# monitor_3.net
KiCad netlist of a schematic drawn in EAGLE
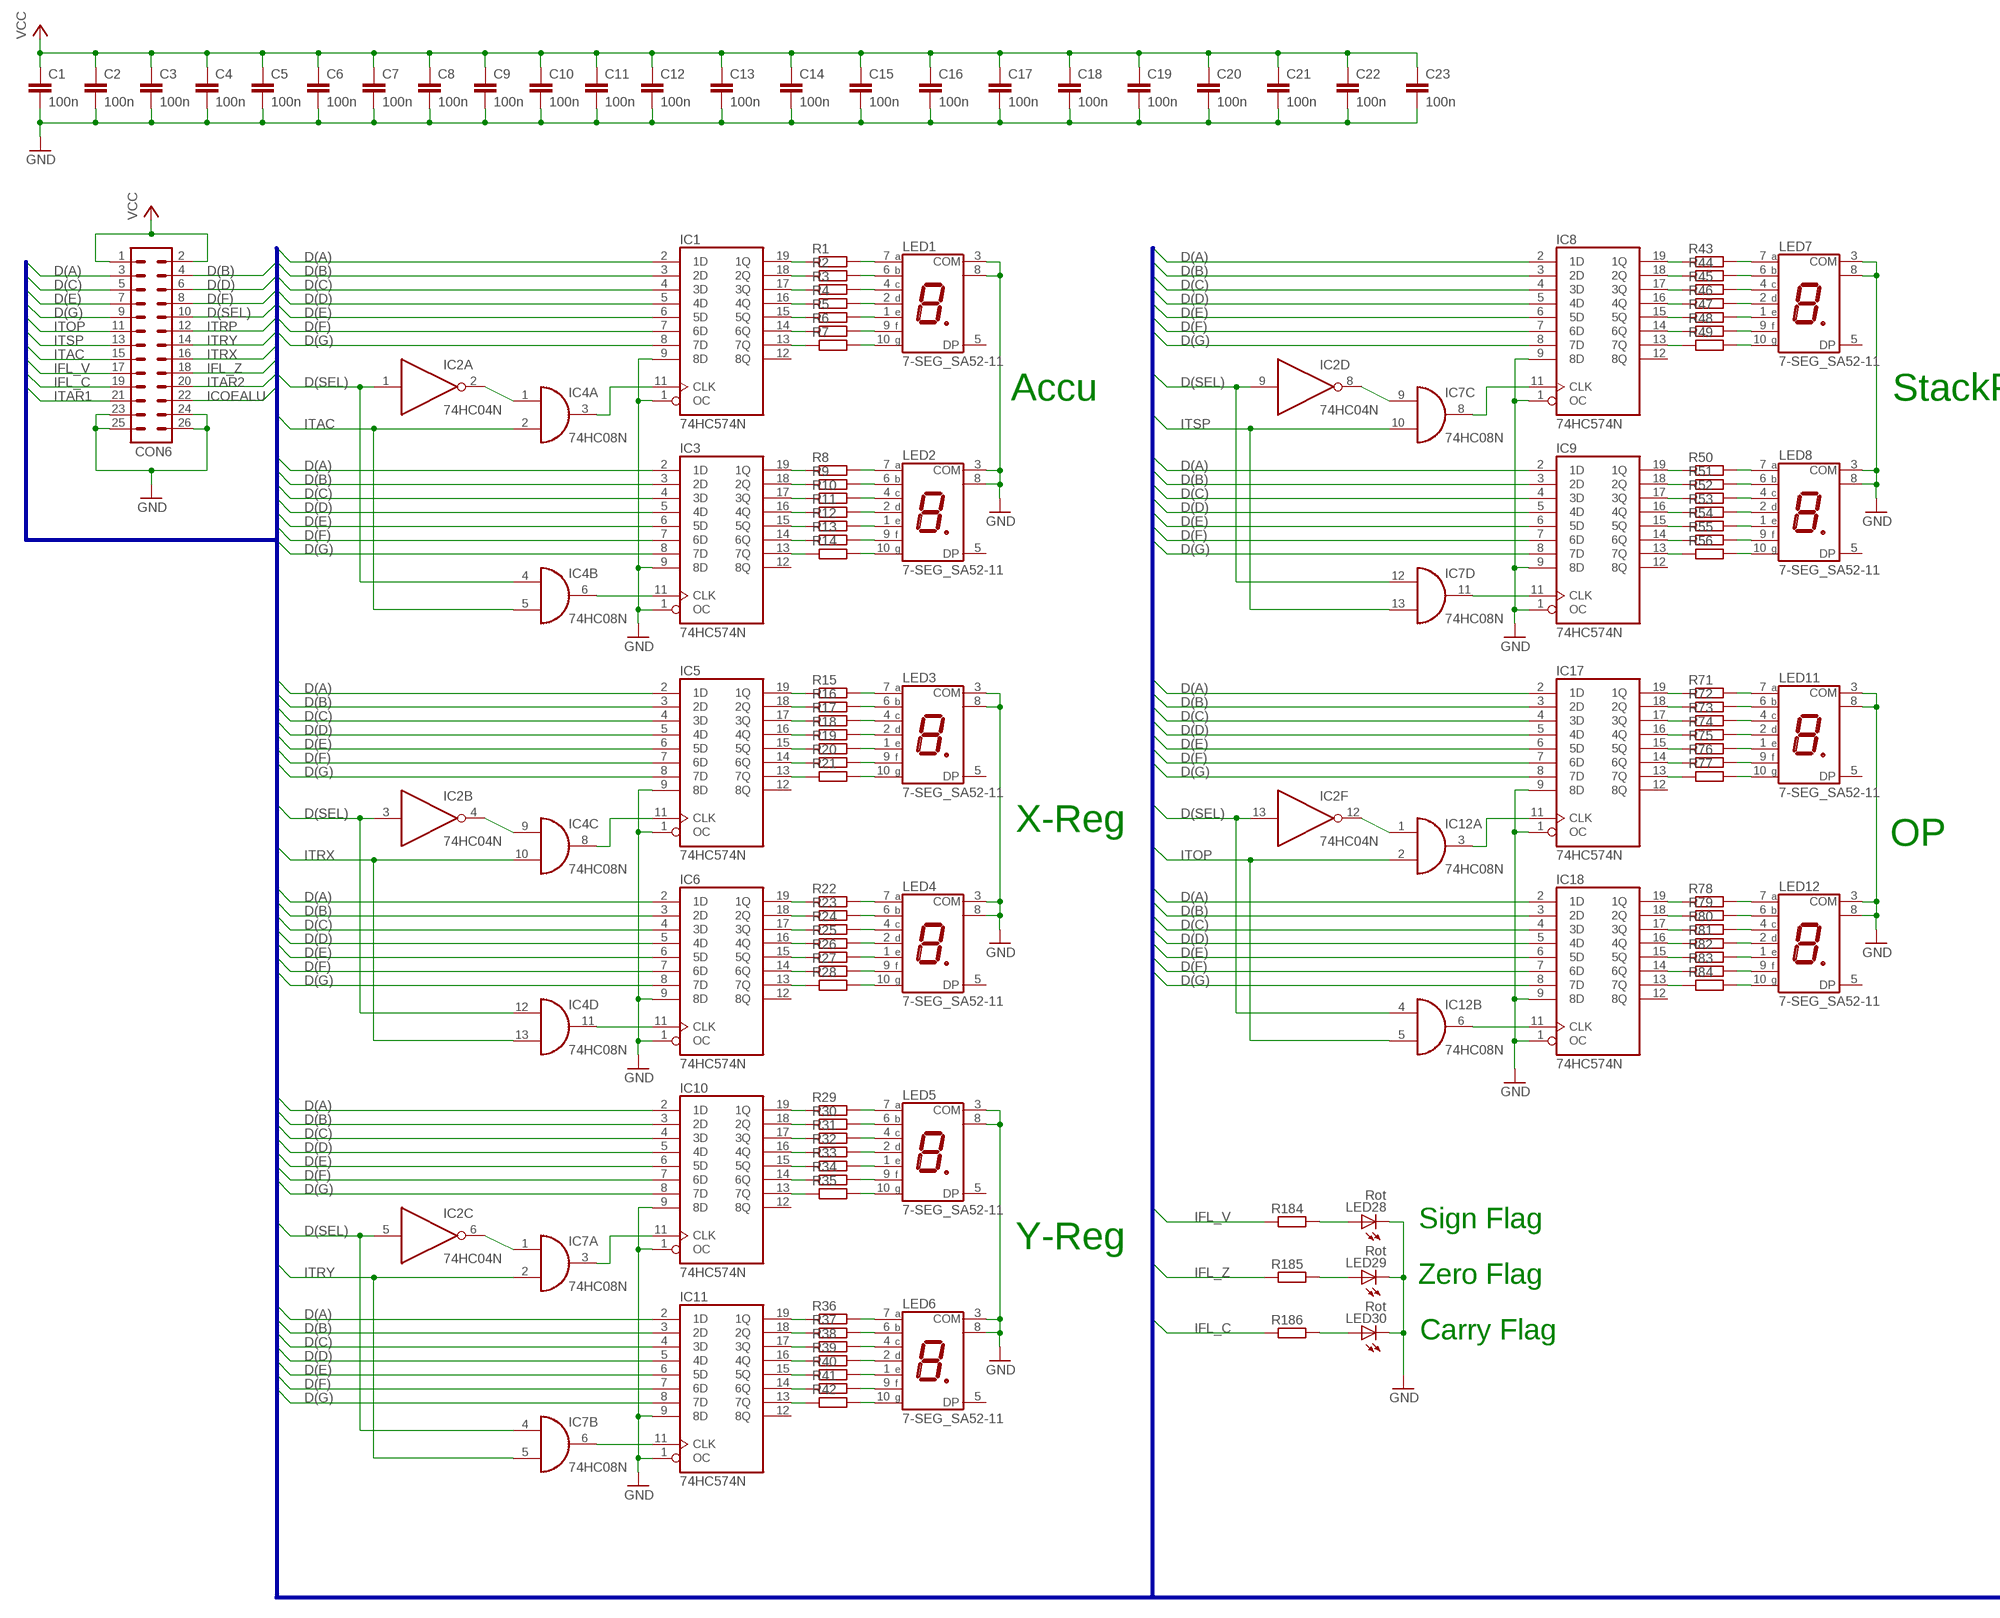
[diagram p0: schematic, sheet 1, part 1 of 2]
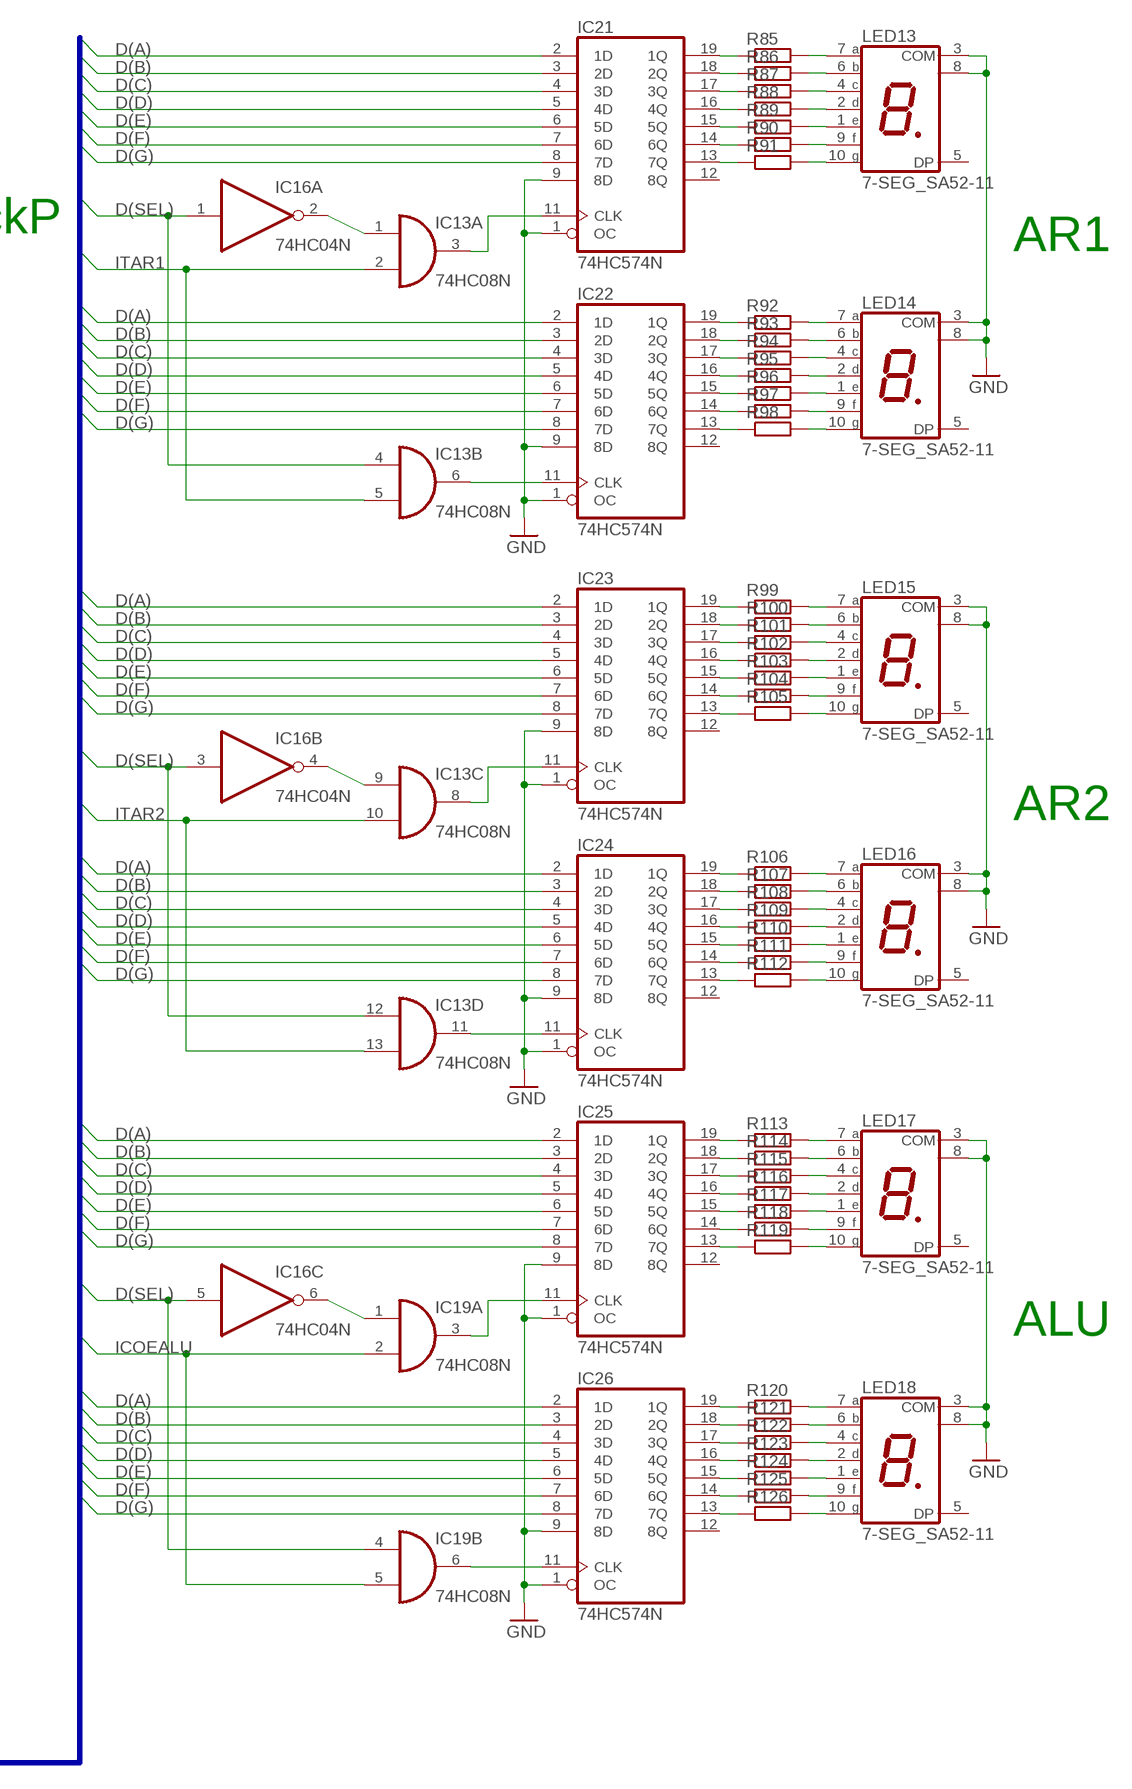
[diagram p1: schematic, sheet 1, part 2 of 2]

(export (version "E")
  (design (tool "Eeschema 10.0.6"))
  (components
    (comp (ref "C1")
      (value "100n")
      (footprint "eagle-import:C025-024X044")
      (libsource (lib "eagle-import") (part "C-EU025-024X044"))
    )
    (comp (ref "C2")
      (value "100n")
      (footprint "eagle-import:C025-024X044")
      (libsource (lib "eagle-import") (part "C-EU025-024X044"))
    )
    (comp (ref "C3")
      (value "100n")
      (footprint "eagle-import:C025-024X044")
      (libsource (lib "eagle-import") (part "C-EU025-024X044"))
    )
    (comp (ref "C4")
      (value "100n")
      (footprint "eagle-import:C025-024X044")
      (libsource (lib "eagle-import") (part "C-EU025-024X044"))
    )
    (comp (ref "C5")
      (value "100n")
      (footprint "eagle-import:C025-024X044")
      (libsource (lib "eagle-import") (part "C-EU025-024X044"))
    )
    (comp (ref "C6")
      (value "100n")
      (footprint "eagle-import:C025-024X044")
      (libsource (lib "eagle-import") (part "C-EU025-024X044"))
    )
    (comp (ref "C7")
      (value "100n")
      (footprint "eagle-import:C025-024X044")
      (libsource (lib "eagle-import") (part "C-EU025-024X044"))
    )
    (comp (ref "C8")
      (value "100n")
      (footprint "eagle-import:C025-024X044")
      (libsource (lib "eagle-import") (part "C-EU025-024X044"))
    )
    (comp (ref "C9")
      (value "100n")
      (footprint "eagle-import:C025-024X044")
      (libsource (lib "eagle-import") (part "C-EU025-024X044"))
    )
    (comp (ref "C10")
      (value "100n")
      (footprint "eagle-import:C025-024X044")
      (libsource (lib "eagle-import") (part "C-EU025-024X044"))
    )
    (comp (ref "C11")
      (value "100n")
      (footprint "eagle-import:C025-024X044")
      (libsource (lib "eagle-import") (part "C-EU025-024X044"))
    )
    (comp (ref "C12")
      (value "100n")
      (footprint "eagle-import:C025-024X044")
      (libsource (lib "eagle-import") (part "C-EU025-024X044"))
    )
    (comp (ref "C13")
      (value "100n")
      (footprint "eagle-import:C025-024X044")
      (libsource (lib "eagle-import") (part "C-EU025-024X044"))
    )
    (comp (ref "C14")
      (value "100n")
      (footprint "eagle-import:C025-024X044")
      (libsource (lib "eagle-import") (part "C-EU025-024X044"))
    )
    (comp (ref "C15")
      (value "100n")
      (footprint "eagle-import:C025-024X044")
      (libsource (lib "eagle-import") (part "C-EU025-024X044"))
    )
    (comp (ref "C16")
      (value "100n")
      (footprint "eagle-import:C025-024X044")
      (libsource (lib "eagle-import") (part "C-EU025-024X044"))
    )
    (comp (ref "C17")
      (value "100n")
      (footprint "eagle-import:C025-024X044")
      (libsource (lib "eagle-import") (part "C-EU025-024X044"))
    )
    (comp (ref "C18")
      (value "100n")
      (footprint "eagle-import:C025-024X044")
      (libsource (lib "eagle-import") (part "C-EU025-024X044"))
    )
    (comp (ref "C19")
      (value "100n")
      (footprint "eagle-import:C025-024X044")
      (libsource (lib "eagle-import") (part "C-EU025-024X044"))
    )
    (comp (ref "C20")
      (value "100n")
      (footprint "eagle-import:C025-024X044")
      (libsource (lib "eagle-import") (part "C-EU025-024X044"))
    )
    (comp (ref "C21")
      (value "100n")
      (footprint "eagle-import:C025-024X044")
      (libsource (lib "eagle-import") (part "C-EU025-024X044"))
    )
    (comp (ref "C22")
      (value "100n")
      (footprint "eagle-import:C025-024X044")
      (libsource (lib "eagle-import") (part "C-EU025-024X044"))
    )
    (comp (ref "C23")
      (value "100n")
      (footprint "eagle-import:C025-024X044")
      (libsource (lib "eagle-import") (part "C-EU025-024X044"))
    )
    (comp (ref "CON6")
      (value "ML26L")
      (footprint "eagle-import:ML26L")
      (libsource (lib "eagle-import") (part "ML26L"))
    )
    (comp (ref "IC1")
      (value "74HC574N")
      (footprint "eagle-import:DIL20")
      (libsource (lib "eagle-import") (part "74574NHC"))
    )
    (comp (ref "IC2")
      (value "74HC04N")
      (footprint "eagle-import:DIL14")
      (libsource (lib "eagle-import") (part "7404NHC"))
    )
    (comp (ref "IC3")
      (value "74HC574N")
      (footprint "eagle-import:DIL20")
      (libsource (lib "eagle-import") (part "74574NHC"))
    )
    (comp (ref "IC4")
      (value "74HC08N")
      (footprint "eagle-import:DIL14")
      (libsource (lib "eagle-import") (part "7408NHC"))
    )
    (comp (ref "IC5")
      (value "74HC574N")
      (footprint "eagle-import:DIL20")
      (libsource (lib "eagle-import") (part "74574NHC"))
    )
    (comp (ref "IC6")
      (value "74HC574N")
      (footprint "eagle-import:DIL20")
      (libsource (lib "eagle-import") (part "74574NHC"))
    )
    (comp (ref "IC7")
      (value "74HC08N")
      (footprint "eagle-import:DIL14")
      (libsource (lib "eagle-import") (part "7408NHC"))
    )
    (comp (ref "IC8")
      (value "74HC574N")
      (footprint "eagle-import:DIL20")
      (libsource (lib "eagle-import") (part "74574NHC"))
    )
    (comp (ref "IC9")
      (value "74HC574N")
      (footprint "eagle-import:DIL20")
      (libsource (lib "eagle-import") (part "74574NHC"))
    )
    (comp (ref "IC10")
      (value "74HC574N")
      (footprint "eagle-import:DIL20")
      (libsource (lib "eagle-import") (part "74574NHC"))
    )
    (comp (ref "IC11")
      (value "74HC574N")
      (footprint "eagle-import:DIL20")
      (libsource (lib "eagle-import") (part "74574NHC"))
    )
    (comp (ref "IC12")
      (value "74HC08N")
      (footprint "eagle-import:DIL14")
      (libsource (lib "eagle-import") (part "7408NHC"))
    )
    (comp (ref "IC13")
      (value "74HC08N")
      (footprint "eagle-import:DIL14")
      (libsource (lib "eagle-import") (part "7408NHC"))
    )
    (comp (ref "IC16")
      (value "74HC04N")
      (footprint "eagle-import:DIL14")
      (libsource (lib "eagle-import") (part "7404NHC"))
    )
    (comp (ref "IC17")
      (value "74HC574N")
      (footprint "eagle-import:DIL20")
      (libsource (lib "eagle-import") (part "74574NHC"))
    )
    (comp (ref "IC18")
      (value "74HC574N")
      (footprint "eagle-import:DIL20")
      (libsource (lib "eagle-import") (part "74574NHC"))
    )
    (comp (ref "IC19")
      (value "74HC08N")
      (footprint "eagle-import:DIL14")
      (libsource (lib "eagle-import") (part "7408NHC"))
    )
    (comp (ref "IC21")
      (value "74HC574N")
      (footprint "eagle-import:DIL20")
      (libsource (lib "eagle-import") (part "74574NHC"))
    )
    (comp (ref "IC22")
      (value "74HC574N")
      (footprint "eagle-import:DIL20")
      (libsource (lib "eagle-import") (part "74574NHC"))
    )
    (comp (ref "IC23")
      (value "74HC574N")
      (footprint "eagle-import:DIL20")
      (libsource (lib "eagle-import") (part "74574NHC"))
    )
    (comp (ref "IC24")
      (value "74HC574N")
      (footprint "eagle-import:DIL20")
      (libsource (lib "eagle-import") (part "74574NHC"))
    )
    (comp (ref "IC25")
      (value "74HC574N")
      (footprint "eagle-import:DIL20")
      (libsource (lib "eagle-import") (part "74574NHC"))
    )
    (comp (ref "IC26")
      (value "74HC574N")
      (footprint "eagle-import:DIL20")
      (libsource (lib "eagle-import") (part "74574NHC"))
    )
    (comp (ref "LED1")
      (value "7-SEG_SA52-11")
      (footprint "eagle-import:SA52-11")
      (libsource (lib "eagle-import") (part "7-SEG_SA52-11"))
    )
    (comp (ref "LED2")
      (value "7-SEG_SA52-11")
      (footprint "eagle-import:SA52-11")
      (libsource (lib "eagle-import") (part "7-SEG_SA52-11"))
    )
    (comp (ref "LED3")
      (value "7-SEG_SA52-11")
      (footprint "eagle-import:SA52-11")
      (libsource (lib "eagle-import") (part "7-SEG_SA52-11"))
    )
    (comp (ref "LED4")
      (value "7-SEG_SA52-11")
      (footprint "eagle-import:SA52-11")
      (libsource (lib "eagle-import") (part "7-SEG_SA52-11"))
    )
    (comp (ref "LED5")
      (value "7-SEG_SA52-11")
      (footprint "eagle-import:SA52-11")
      (libsource (lib "eagle-import") (part "7-SEG_SA52-11"))
    )
    (comp (ref "LED6")
      (value "7-SEG_SA52-11")
      (footprint "eagle-import:SA52-11")
      (libsource (lib "eagle-import") (part "7-SEG_SA52-11"))
    )
    (comp (ref "LED7")
      (value "7-SEG_SA52-11")
      (footprint "eagle-import:SA52-11")
      (libsource (lib "eagle-import") (part "7-SEG_SA52-11"))
    )
    (comp (ref "LED8")
      (value "7-SEG_SA52-11")
      (footprint "eagle-import:SA52-11")
      (libsource (lib "eagle-import") (part "7-SEG_SA52-11"))
    )
    (comp (ref "LED11")
      (value "7-SEG_SA52-11")
      (footprint "eagle-import:SA52-11")
      (libsource (lib "eagle-import") (part "7-SEG_SA52-11"))
    )
    (comp (ref "LED12")
      (value "7-SEG_SA52-11")
      (footprint "eagle-import:SA52-11")
      (libsource (lib "eagle-import") (part "7-SEG_SA52-11"))
    )
    (comp (ref "LED13")
      (value "7-SEG_SA52-11")
      (footprint "eagle-import:SA52-11")
      (libsource (lib "eagle-import") (part "7-SEG_SA52-11"))
    )
    (comp (ref "LED14")
      (value "7-SEG_SA52-11")
      (footprint "eagle-import:SA52-11")
      (libsource (lib "eagle-import") (part "7-SEG_SA52-11"))
    )
    (comp (ref "LED15")
      (value "7-SEG_SA52-11")
      (footprint "eagle-import:SA52-11")
      (libsource (lib "eagle-import") (part "7-SEG_SA52-11"))
    )
    (comp (ref "LED16")
      (value "7-SEG_SA52-11")
      (footprint "eagle-import:SA52-11")
      (libsource (lib "eagle-import") (part "7-SEG_SA52-11"))
    )
    (comp (ref "LED17")
      (value "7-SEG_SA52-11")
      (footprint "eagle-import:SA52-11")
      (libsource (lib "eagle-import") (part "7-SEG_SA52-11"))
    )
    (comp (ref "LED18")
      (value "7-SEG_SA52-11")
      (footprint "eagle-import:SA52-11")
      (libsource (lib "eagle-import") (part "7-SEG_SA52-11"))
    )
    (comp (ref "LED28")
      (value "Rot")
      (footprint "eagle-import:LED5MM")
      (libsource (lib "eagle-import") (part "LED5MM"))
    )
    (comp (ref "LED29")
      (value "Rot")
      (footprint "eagle-import:LED5MM")
      (libsource (lib "eagle-import") (part "LED5MM"))
    )
    (comp (ref "LED30")
      (value "Rot")
      (footprint "eagle-import:LED5MM")
      (libsource (lib "eagle-import") (part "LED5MM"))
    )
    (comp (ref "R1")
      (value "R-EU_0207/7")
      (footprint "eagle-import:0207_7")
      (libsource (lib "eagle-import") (part "R-EU_0207/7"))
    )
    (comp (ref "R2")
      (value "R-EU_0207/7")
      (footprint "eagle-import:0207_7")
      (libsource (lib "eagle-import") (part "R-EU_0207/7"))
    )
    (comp (ref "R3")
      (value "R-EU_0207/7")
      (footprint "eagle-import:0207_7")
      (libsource (lib "eagle-import") (part "R-EU_0207/7"))
    )
    (comp (ref "R4")
      (value "R-EU_0207/7")
      (footprint "eagle-import:0207_7")
      (libsource (lib "eagle-import") (part "R-EU_0207/7"))
    )
    (comp (ref "R5")
      (value "R-EU_0207/7")
      (footprint "eagle-import:0207_7")
      (libsource (lib "eagle-import") (part "R-EU_0207/7"))
    )
    (comp (ref "R6")
      (value "R-EU_0207/7")
      (footprint "eagle-import:0207_7")
      (libsource (lib "eagle-import") (part "R-EU_0207/7"))
    )
    (comp (ref "R7")
      (value "R-EU_0207/7")
      (footprint "eagle-import:0207_7")
      (libsource (lib "eagle-import") (part "R-EU_0207/7"))
    )
    (comp (ref "R8")
      (value "R-EU_0207/7")
      (footprint "eagle-import:0207_7")
      (libsource (lib "eagle-import") (part "R-EU_0207/7"))
    )
    (comp (ref "R9")
      (value "R-EU_0207/7")
      (footprint "eagle-import:0207_7")
      (libsource (lib "eagle-import") (part "R-EU_0207/7"))
    )
    (comp (ref "R10")
      (value "R-EU_0207/7")
      (footprint "eagle-import:0207_7")
      (libsource (lib "eagle-import") (part "R-EU_0207/7"))
    )
    (comp (ref "R11")
      (value "R-EU_0207/7")
      (footprint "eagle-import:0207_7")
      (libsource (lib "eagle-import") (part "R-EU_0207/7"))
    )
    (comp (ref "R12")
      (value "R-EU_0207/7")
      (footprint "eagle-import:0207_7")
      (libsource (lib "eagle-import") (part "R-EU_0207/7"))
    )
    (comp (ref "R13")
      (value "R-EU_0207/7")
      (footprint "eagle-import:0207_7")
      (libsource (lib "eagle-import") (part "R-EU_0207/7"))
    )
    (comp (ref "R14")
      (value "R-EU_0207/7")
      (footprint "eagle-import:0207_7")
      (libsource (lib "eagle-import") (part "R-EU_0207/7"))
    )
    (comp (ref "R15")
      (value "R-EU_0207/7")
      (footprint "eagle-import:0207_7")
      (libsource (lib "eagle-import") (part "R-EU_0207/7"))
    )
    (comp (ref "R16")
      (value "R-EU_0207/7")
      (footprint "eagle-import:0207_7")
      (libsource (lib "eagle-import") (part "R-EU_0207/7"))
    )
    (comp (ref "R17")
      (value "R-EU_0207/7")
      (footprint "eagle-import:0207_7")
      (libsource (lib "eagle-import") (part "R-EU_0207/7"))
    )
    (comp (ref "R18")
      (value "R-EU_0207/7")
      (footprint "eagle-import:0207_7")
      (libsource (lib "eagle-import") (part "R-EU_0207/7"))
    )
    (comp (ref "R19")
      (value "R-EU_0207/7")
      (footprint "eagle-import:0207_7")
      (libsource (lib "eagle-import") (part "R-EU_0207/7"))
    )
    (comp (ref "R20")
      (value "R-EU_0207/7")
      (footprint "eagle-import:0207_7")
      (libsource (lib "eagle-import") (part "R-EU_0207/7"))
    )
    (comp (ref "R21")
      (value "R-EU_0207/7")
      (footprint "eagle-import:0207_7")
      (libsource (lib "eagle-import") (part "R-EU_0207/7"))
    )
    (comp (ref "R22")
      (value "R-EU_0207/7")
      (footprint "eagle-import:0207_7")
      (libsource (lib "eagle-import") (part "R-EU_0207/7"))
    )
    (comp (ref "R23")
      (value "R-EU_0207/7")
      (footprint "eagle-import:0207_7")
      (libsource (lib "eagle-import") (part "R-EU_0207/7"))
    )
    (comp (ref "R24")
      (value "R-EU_0207/7")
      (footprint "eagle-import:0207_7")
      (libsource (lib "eagle-import") (part "R-EU_0207/7"))
    )
    (comp (ref "R25")
      (value "R-EU_0207/7")
      (footprint "eagle-import:0207_7")
      (libsource (lib "eagle-import") (part "R-EU_0207/7"))
    )
    (comp (ref "R26")
      (value "R-EU_0207/7")
      (footprint "eagle-import:0207_7")
      (libsource (lib "eagle-import") (part "R-EU_0207/7"))
    )
    (comp (ref "R27")
      (value "R-EU_0207/7")
      (footprint "eagle-import:0207_7")
      (libsource (lib "eagle-import") (part "R-EU_0207/7"))
    )
    (comp (ref "R28")
      (value "R-EU_0207/7")
      (footprint "eagle-import:0207_7")
      (libsource (lib "eagle-import") (part "R-EU_0207/7"))
    )
    (comp (ref "R29")
      (value "R-EU_0207/7")
      (footprint "eagle-import:0207_7")
      (libsource (lib "eagle-import") (part "R-EU_0207/7"))
    )
    (comp (ref "R30")
      (value "R-EU_0207/7")
      (footprint "eagle-import:0207_7")
      (libsource (lib "eagle-import") (part "R-EU_0207/7"))
    )
    (comp (ref "R31")
      (value "R-EU_0207/7")
      (footprint "eagle-import:0207_7")
      (libsource (lib "eagle-import") (part "R-EU_0207/7"))
    )
    (comp (ref "R32")
      (value "R-EU_0207/7")
      (footprint "eagle-import:0207_7")
      (libsource (lib "eagle-import") (part "R-EU_0207/7"))
    )
    (comp (ref "R33")
      (value "R-EU_0207/7")
      (footprint "eagle-import:0207_7")
      (libsource (lib "eagle-import") (part "R-EU_0207/7"))
    )
    (comp (ref "R34")
      (value "R-EU_0207/7")
      (footprint "eagle-import:0207_7")
      (libsource (lib "eagle-import") (part "R-EU_0207/7"))
    )
    (comp (ref "R35")
      (value "R-EU_0207/7")
      (footprint "eagle-import:0207_7")
      (libsource (lib "eagle-import") (part "R-EU_0207/7"))
    )
    (comp (ref "R36")
      (value "R-EU_0207/7")
      (footprint "eagle-import:0207_7")
      (libsource (lib "eagle-import") (part "R-EU_0207/7"))
    )
    (comp (ref "R37")
      (value "R-EU_0207/7")
      (footprint "eagle-import:0207_7")
      (libsource (lib "eagle-import") (part "R-EU_0207/7"))
    )
    (comp (ref "R38")
      (value "R-EU_0207/7")
      (footprint "eagle-import:0207_7")
      (libsource (lib "eagle-import") (part "R-EU_0207/7"))
    )
    (comp (ref "R39")
      (value "R-EU_0207/7")
      (footprint "eagle-import:0207_7")
      (libsource (lib "eagle-import") (part "R-EU_0207/7"))
    )
    (comp (ref "R40")
      (value "R-EU_0207/7")
      (footprint "eagle-import:0207_7")
      (libsource (lib "eagle-import") (part "R-EU_0207/7"))
    )
    (comp (ref "R41")
      (value "R-EU_0207/7")
      (footprint "eagle-import:0207_7")
      (libsource (lib "eagle-import") (part "R-EU_0207/7"))
    )
    (comp (ref "R42")
      (value "R-EU_0207/7")
      (footprint "eagle-import:0207_7")
      (libsource (lib "eagle-import") (part "R-EU_0207/7"))
    )
    (comp (ref "R43")
      (value "R-EU_0207/7")
      (footprint "eagle-import:0207_7")
      (libsource (lib "eagle-import") (part "R-EU_0207/7"))
    )
    (comp (ref "R44")
      (value "R-EU_0207/7")
      (footprint "eagle-import:0207_7")
      (libsource (lib "eagle-import") (part "R-EU_0207/7"))
    )
    (comp (ref "R45")
      (value "R-EU_0207/7")
      (footprint "eagle-import:0207_7")
      (libsource (lib "eagle-import") (part "R-EU_0207/7"))
    )
    (comp (ref "R46")
      (value "R-EU_0207/7")
      (footprint "eagle-import:0207_7")
      (libsource (lib "eagle-import") (part "R-EU_0207/7"))
    )
    (comp (ref "R47")
      (value "R-EU_0207/7")
      (footprint "eagle-import:0207_7")
      (libsource (lib "eagle-import") (part "R-EU_0207/7"))
    )
    (comp (ref "R48")
      (value "R-EU_0207/7")
      (footprint "eagle-import:0207_7")
      (libsource (lib "eagle-import") (part "R-EU_0207/7"))
    )
    (comp (ref "R49")
      (value "R-EU_0207/7")
      (footprint "eagle-import:0207_7")
      (libsource (lib "eagle-import") (part "R-EU_0207/7"))
    )
    (comp (ref "R50")
      (value "R-EU_0207/7")
      (footprint "eagle-import:0207_7")
      (libsource (lib "eagle-import") (part "R-EU_0207/7"))
    )
    (comp (ref "R51")
      (value "R-EU_0207/7")
      (footprint "eagle-import:0207_7")
      (libsource (lib "eagle-import") (part "R-EU_0207/7"))
    )
    (comp (ref "R52")
      (value "R-EU_0207/7")
      (footprint "eagle-import:0207_7")
      (libsource (lib "eagle-import") (part "R-EU_0207/7"))
    )
    (comp (ref "R53")
      (value "R-EU_0207/7")
      (footprint "eagle-import:0207_7")
      (libsource (lib "eagle-import") (part "R-EU_0207/7"))
    )
    (comp (ref "R54")
      (value "R-EU_0207/7")
      (footprint "eagle-import:0207_7")
      (libsource (lib "eagle-import") (part "R-EU_0207/7"))
    )
    (comp (ref "R55")
      (value "R-EU_0207/7")
      (footprint "eagle-import:0207_7")
      (libsource (lib "eagle-import") (part "R-EU_0207/7"))
    )
    (comp (ref "R56")
      (value "R-EU_0207/7")
      (footprint "eagle-import:0207_7")
      (libsource (lib "eagle-import") (part "R-EU_0207/7"))
    )
    (comp (ref "R71")
      (value "R-EU_0207/7")
      (footprint "eagle-import:0207_7")
      (libsource (lib "eagle-import") (part "R-EU_0207/7"))
    )
    (comp (ref "R72")
      (value "R-EU_0207/7")
      (footprint "eagle-import:0207_7")
      (libsource (lib "eagle-import") (part "R-EU_0207/7"))
    )
    (comp (ref "R73")
      (value "R-EU_0207/7")
      (footprint "eagle-import:0207_7")
      (libsource (lib "eagle-import") (part "R-EU_0207/7"))
    )
    (comp (ref "R74")
      (value "R-EU_0207/7")
      (footprint "eagle-import:0207_7")
      (libsource (lib "eagle-import") (part "R-EU_0207/7"))
    )
    (comp (ref "R75")
      (value "R-EU_0207/7")
      (footprint "eagle-import:0207_7")
      (libsource (lib "eagle-import") (part "R-EU_0207/7"))
    )
    (comp (ref "R76")
      (value "R-EU_0207/7")
      (footprint "eagle-import:0207_7")
      (libsource (lib "eagle-import") (part "R-EU_0207/7"))
    )
    (comp (ref "R77")
      (value "R-EU_0207/7")
      (footprint "eagle-import:0207_7")
      (libsource (lib "eagle-import") (part "R-EU_0207/7"))
    )
    (comp (ref "R78")
      (value "R-EU_0207/7")
      (footprint "eagle-import:0207_7")
      (libsource (lib "eagle-import") (part "R-EU_0207/7"))
    )
    (comp (ref "R79")
      (value "R-EU_0207/7")
      (footprint "eagle-import:0207_7")
      (libsource (lib "eagle-import") (part "R-EU_0207/7"))
    )
    (comp (ref "R80")
      (value "R-EU_0207/7")
      (footprint "eagle-import:0207_7")
      (libsource (lib "eagle-import") (part "R-EU_0207/7"))
    )
    (comp (ref "R81")
      (value "R-EU_0207/7")
      (footprint "eagle-import:0207_7")
      (libsource (lib "eagle-import") (part "R-EU_0207/7"))
    )
    (comp (ref "R82")
      (value "R-EU_0207/7")
      (footprint "eagle-import:0207_7")
      (libsource (lib "eagle-import") (part "R-EU_0207/7"))
    )
    (comp (ref "R83")
      (value "R-EU_0207/7")
      (footprint "eagle-import:0207_7")
      (libsource (lib "eagle-import") (part "R-EU_0207/7"))
    )
    (comp (ref "R84")
      (value "R-EU_0207/7")
      (footprint "eagle-import:0207_7")
      (libsource (lib "eagle-import") (part "R-EU_0207/7"))
    )
    (comp (ref "R85")
      (value "R-EU_0207/7")
      (footprint "eagle-import:0207_7")
      (libsource (lib "eagle-import") (part "R-EU_0207/7"))
    )
    (comp (ref "R86")
      (value "R-EU_0207/7")
      (footprint "eagle-import:0207_7")
      (libsource (lib "eagle-import") (part "R-EU_0207/7"))
    )
    (comp (ref "R87")
      (value "R-EU_0207/7")
      (footprint "eagle-import:0207_7")
      (libsource (lib "eagle-import") (part "R-EU_0207/7"))
    )
    (comp (ref "R88")
      (value "R-EU_0207/7")
      (footprint "eagle-import:0207_7")
      (libsource (lib "eagle-import") (part "R-EU_0207/7"))
    )
    (comp (ref "R89")
      (value "R-EU_0207/7")
      (footprint "eagle-import:0207_7")
      (libsource (lib "eagle-import") (part "R-EU_0207/7"))
    )
    (comp (ref "R90")
      (value "R-EU_0207/7")
      (footprint "eagle-import:0207_7")
      (libsource (lib "eagle-import") (part "R-EU_0207/7"))
    )
    (comp (ref "R91")
      (value "R-EU_0207/7")
      (footprint "eagle-import:0207_7")
      (libsource (lib "eagle-import") (part "R-EU_0207/7"))
    )
    (comp (ref "R92")
      (value "R-EU_0207/7")
      (footprint "eagle-import:0207_7")
      (libsource (lib "eagle-import") (part "R-EU_0207/7"))
    )
    (comp (ref "R93")
      (value "R-EU_0207/7")
      (footprint "eagle-import:0207_7")
      (libsource (lib "eagle-import") (part "R-EU_0207/7"))
    )
    (comp (ref "R94")
      (value "R-EU_0207/7")
      (footprint "eagle-import:0207_7")
      (libsource (lib "eagle-import") (part "R-EU_0207/7"))
    )
    (comp (ref "R95")
      (value "R-EU_0207/7")
      (footprint "eagle-import:0207_7")
      (libsource (lib "eagle-import") (part "R-EU_0207/7"))
    )
    (comp (ref "R96")
      (value "R-EU_0207/7")
      (footprint "eagle-import:0207_7")
      (libsource (lib "eagle-import") (part "R-EU_0207/7"))
    )
    (comp (ref "R97")
      (value "R-EU_0207/7")
      (footprint "eagle-import:0207_7")
      (libsource (lib "eagle-import") (part "R-EU_0207/7"))
    )
    (comp (ref "R98")
      (value "R-EU_0207/7")
      (footprint "eagle-import:0207_7")
      (libsource (lib "eagle-import") (part "R-EU_0207/7"))
    )
    (comp (ref "R99")
      (value "R-EU_0207/7")
      (footprint "eagle-import:0207_7")
      (libsource (lib "eagle-import") (part "R-EU_0207/7"))
    )
    (comp (ref "R100")
      (value "R-EU_0207/7")
      (footprint "eagle-import:0207_7")
      (libsource (lib "eagle-import") (part "R-EU_0207/7"))
    )
    (comp (ref "R101")
      (value "R-EU_0207/7")
      (footprint "eagle-import:0207_7")
      (libsource (lib "eagle-import") (part "R-EU_0207/7"))
    )
    (comp (ref "R102")
      (value "R-EU_0207/7")
      (footprint "eagle-import:0207_7")
      (libsource (lib "eagle-import") (part "R-EU_0207/7"))
    )
    (comp (ref "R103")
      (value "R-EU_0207/7")
      (footprint "eagle-import:0207_7")
      (libsource (lib "eagle-import") (part "R-EU_0207/7"))
    )
    (comp (ref "R104")
      (value "R-EU_0207/7")
      (footprint "eagle-import:0207_7")
      (libsource (lib "eagle-import") (part "R-EU_0207/7"))
    )
    (comp (ref "R105")
      (value "R-EU_0207/7")
      (footprint "eagle-import:0207_7")
      (libsource (lib "eagle-import") (part "R-EU_0207/7"))
    )
    (comp (ref "R106")
      (value "R-EU_0207/7")
      (footprint "eagle-import:0207_7")
      (libsource (lib "eagle-import") (part "R-EU_0207/7"))
    )
    (comp (ref "R107")
      (value "R-EU_0207/7")
      (footprint "eagle-import:0207_7")
      (libsource (lib "eagle-import") (part "R-EU_0207/7"))
    )
    (comp (ref "R108")
      (value "R-EU_0207/7")
      (footprint "eagle-import:0207_7")
      (libsource (lib "eagle-import") (part "R-EU_0207/7"))
    )
    (comp (ref "R109")
      (value "R-EU_0207/7")
      (footprint "eagle-import:0207_7")
      (libsource (lib "eagle-import") (part "R-EU_0207/7"))
    )
    (comp (ref "R110")
      (value "R-EU_0207/7")
      (footprint "eagle-import:0207_7")
      (libsource (lib "eagle-import") (part "R-EU_0207/7"))
    )
    (comp (ref "R111")
      (value "R-EU_0207/7")
      (footprint "eagle-import:0207_7")
      (libsource (lib "eagle-import") (part "R-EU_0207/7"))
    )
    (comp (ref "R112")
      (value "R-EU_0207/7")
      (footprint "eagle-import:0207_7")
      (libsource (lib "eagle-import") (part "R-EU_0207/7"))
    )
    (comp (ref "R113")
      (value "R-EU_0207/7")
      (footprint "eagle-import:0207_7")
      (libsource (lib "eagle-import") (part "R-EU_0207/7"))
    )
    (comp (ref "R114")
      (value "R-EU_0207/7")
      (footprint "eagle-import:0207_7")
      (libsource (lib "eagle-import") (part "R-EU_0207/7"))
    )
    (comp (ref "R115")
      (value "R-EU_0207/7")
      (footprint "eagle-import:0207_7")
      (libsource (lib "eagle-import") (part "R-EU_0207/7"))
    )
    (comp (ref "R116")
      (value "R-EU_0207/7")
      (footprint "eagle-import:0207_7")
      (libsource (lib "eagle-import") (part "R-EU_0207/7"))
    )
    (comp (ref "R117")
      (value "R-EU_0207/7")
      (footprint "eagle-import:0207_7")
      (libsource (lib "eagle-import") (part "R-EU_0207/7"))
    )
    (comp (ref "R118")
      (value "R-EU_0207/7")
      (footprint "eagle-import:0207_7")
      (libsource (lib "eagle-import") (part "R-EU_0207/7"))
    )
    (comp (ref "R119")
      (value "R-EU_0207/7")
      (footprint "eagle-import:0207_7")
      (libsource (lib "eagle-import") (part "R-EU_0207/7"))
    )
    (comp (ref "R120")
      (value "R-EU_0207/7")
      (footprint "eagle-import:0207_7")
      (libsource (lib "eagle-import") (part "R-EU_0207/7"))
    )
    (comp (ref "R121")
      (value "R-EU_0207/7")
      (footprint "eagle-import:0207_7")
      (libsource (lib "eagle-import") (part "R-EU_0207/7"))
    )
    (comp (ref "R122")
      (value "R-EU_0207/7")
      (footprint "eagle-import:0207_7")
      (libsource (lib "eagle-import") (part "R-EU_0207/7"))
    )
    (comp (ref "R123")
      (value "R-EU_0207/7")
      (footprint "eagle-import:0207_7")
      (libsource (lib "eagle-import") (part "R-EU_0207/7"))
    )
    (comp (ref "R124")
      (value "R-EU_0207/7")
      (footprint "eagle-import:0207_7")
      (libsource (lib "eagle-import") (part "R-EU_0207/7"))
    )
    (comp (ref "R125")
      (value "R-EU_0207/7")
      (footprint "eagle-import:0207_7")
      (libsource (lib "eagle-import") (part "R-EU_0207/7"))
    )
    (comp (ref "R126")
      (value "R-EU_0207/7")
      (footprint "eagle-import:0207_7")
      (libsource (lib "eagle-import") (part "R-EU_0207/7"))
    )
    (comp (ref "R184")
      (value "R-EU_0207/7")
      (footprint "eagle-import:0207_7")
      (libsource (lib "eagle-import") (part "R-EU_0207/7"))
    )
    (comp (ref "R185")
      (value "R-EU_0207/7")
      (footprint "eagle-import:0207_7")
      (libsource (lib "eagle-import") (part "R-EU_0207/7"))
    )
    (comp (ref "R186")
      (value "R-EU_0207/7")
      (footprint "eagle-import:0207_7")
      (libsource (lib "eagle-import") (part "R-EU_0207/7"))
    )
  )
  (nets
    (net (code "1") (name "/D(A)") (class "Default")
      (node (ref "CON6") (pin "3") (pinfunction "3_3") (pintype "passive"))
      (node (ref "IC1") (pin "2") (pinfunction "1D_2") (pintype "input"))
      (node (ref "IC10") (pin "2") (pinfunction "1D_2") (pintype "input"))
      (node (ref "IC11") (pin "2") (pinfunction "1D_2") (pintype "input"))
      (node (ref "IC17") (pin "2") (pinfunction "1D_2") (pintype "input"))
      (node (ref "IC18") (pin "2") (pinfunction "1D_2") (pintype "input"))
      (node (ref "IC21") (pin "2") (pinfunction "1D_2") (pintype "input"))
      (node (ref "IC22") (pin "2") (pinfunction "1D_2") (pintype "input"))
      (node (ref "IC23") (pin "2") (pinfunction "1D_2") (pintype "input"))
      (node (ref "IC24") (pin "2") (pinfunction "1D_2") (pintype "input"))
      (node (ref "IC25") (pin "2") (pinfunction "1D_2") (pintype "input"))
      (node (ref "IC26") (pin "2") (pinfunction "1D_2") (pintype "input"))
      (node (ref "IC3") (pin "2") (pinfunction "1D_2") (pintype "input"))
      (node (ref "IC5") (pin "2") (pinfunction "1D_2") (pintype "input"))
      (node (ref "IC6") (pin "2") (pinfunction "1D_2") (pintype "input"))
      (node (ref "IC8") (pin "2") (pinfunction "1D_2") (pintype "input"))
      (node (ref "IC9") (pin "2") (pinfunction "1D_2") (pintype "input"))
    )
    (net (code "2") (name "/D(B)") (class "Default")
      (node (ref "CON6") (pin "4") (pinfunction "4_4") (pintype "passive"))
      (node (ref "IC1") (pin "3") (pinfunction "2D_3") (pintype "input"))
      (node (ref "IC10") (pin "3") (pinfunction "2D_3") (pintype "input"))
      (node (ref "IC11") (pin "3") (pinfunction "2D_3") (pintype "input"))
      (node (ref "IC17") (pin "3") (pinfunction "2D_3") (pintype "input"))
      (node (ref "IC18") (pin "3") (pinfunction "2D_3") (pintype "input"))
      (node (ref "IC21") (pin "3") (pinfunction "2D_3") (pintype "input"))
      (node (ref "IC22") (pin "3") (pinfunction "2D_3") (pintype "input"))
      (node (ref "IC23") (pin "3") (pinfunction "2D_3") (pintype "input"))
      (node (ref "IC24") (pin "3") (pinfunction "2D_3") (pintype "input"))
      (node (ref "IC25") (pin "3") (pinfunction "2D_3") (pintype "input"))
      (node (ref "IC26") (pin "3") (pinfunction "2D_3") (pintype "input"))
      (node (ref "IC3") (pin "3") (pinfunction "2D_3") (pintype "input"))
      (node (ref "IC5") (pin "3") (pinfunction "2D_3") (pintype "input"))
      (node (ref "IC6") (pin "3") (pinfunction "2D_3") (pintype "input"))
      (node (ref "IC8") (pin "3") (pinfunction "2D_3") (pintype "input"))
      (node (ref "IC9") (pin "3") (pinfunction "2D_3") (pintype "input"))
    )
    (net (code "3") (name "/D(C)") (class "Default")
      (node (ref "CON6") (pin "5") (pinfunction "5_5") (pintype "passive"))
      (node (ref "IC1") (pin "4") (pinfunction "3D_4") (pintype "input"))
      (node (ref "IC10") (pin "4") (pinfunction "3D_4") (pintype "input"))
      (node (ref "IC11") (pin "4") (pinfunction "3D_4") (pintype "input"))
      (node (ref "IC17") (pin "4") (pinfunction "3D_4") (pintype "input"))
      (node (ref "IC18") (pin "4") (pinfunction "3D_4") (pintype "input"))
      (node (ref "IC21") (pin "4") (pinfunction "3D_4") (pintype "input"))
      (node (ref "IC22") (pin "4") (pinfunction "3D_4") (pintype "input"))
      (node (ref "IC23") (pin "4") (pinfunction "3D_4") (pintype "input"))
      (node (ref "IC24") (pin "4") (pinfunction "3D_4") (pintype "input"))
      (node (ref "IC25") (pin "4") (pinfunction "3D_4") (pintype "input"))
      (node (ref "IC26") (pin "4") (pinfunction "3D_4") (pintype "input"))
      (node (ref "IC3") (pin "4") (pinfunction "3D_4") (pintype "input"))
      (node (ref "IC5") (pin "4") (pinfunction "3D_4") (pintype "input"))
      (node (ref "IC6") (pin "4") (pinfunction "3D_4") (pintype "input"))
      (node (ref "IC8") (pin "4") (pinfunction "3D_4") (pintype "input"))
      (node (ref "IC9") (pin "4") (pinfunction "3D_4") (pintype "input"))
    )
    (net (code "4") (name "/D(D)") (class "Default")
      (node (ref "CON6") (pin "6") (pinfunction "6_6") (pintype "passive"))
      (node (ref "IC1") (pin "5") (pinfunction "4D_5") (pintype "input"))
      (node (ref "IC10") (pin "5") (pinfunction "4D_5") (pintype "input"))
      (node (ref "IC11") (pin "5") (pinfunction "4D_5") (pintype "input"))
      (node (ref "IC17") (pin "5") (pinfunction "4D_5") (pintype "input"))
      (node (ref "IC18") (pin "5") (pinfunction "4D_5") (pintype "input"))
      (node (ref "IC21") (pin "5") (pinfunction "4D_5") (pintype "input"))
      (node (ref "IC22") (pin "5") (pinfunction "4D_5") (pintype "input"))
      (node (ref "IC23") (pin "5") (pinfunction "4D_5") (pintype "input"))
      (node (ref "IC24") (pin "5") (pinfunction "4D_5") (pintype "input"))
      (node (ref "IC25") (pin "5") (pinfunction "4D_5") (pintype "input"))
      (node (ref "IC26") (pin "5") (pinfunction "4D_5") (pintype "input"))
      (node (ref "IC3") (pin "5") (pinfunction "4D_5") (pintype "input"))
      (node (ref "IC5") (pin "5") (pinfunction "4D_5") (pintype "input"))
      (node (ref "IC6") (pin "5") (pinfunction "4D_5") (pintype "input"))
      (node (ref "IC8") (pin "5") (pinfunction "4D_5") (pintype "input"))
      (node (ref "IC9") (pin "5") (pinfunction "4D_5") (pintype "input"))
    )
    (net (code "5") (name "/D(E)") (class "Default")
      (node (ref "CON6") (pin "7") (pinfunction "7_7") (pintype "passive"))
      (node (ref "IC1") (pin "6") (pinfunction "5D_6") (pintype "input"))
      (node (ref "IC10") (pin "6") (pinfunction "5D_6") (pintype "input"))
      (node (ref "IC11") (pin "6") (pinfunction "5D_6") (pintype "input"))
      (node (ref "IC17") (pin "6") (pinfunction "5D_6") (pintype "input"))
      (node (ref "IC18") (pin "6") (pinfunction "5D_6") (pintype "input"))
      (node (ref "IC21") (pin "6") (pinfunction "5D_6") (pintype "input"))
      (node (ref "IC22") (pin "6") (pinfunction "5D_6") (pintype "input"))
      (node (ref "IC23") (pin "6") (pinfunction "5D_6") (pintype "input"))
      (node (ref "IC24") (pin "6") (pinfunction "5D_6") (pintype "input"))
      (node (ref "IC25") (pin "6") (pinfunction "5D_6") (pintype "input"))
      (node (ref "IC26") (pin "6") (pinfunction "5D_6") (pintype "input"))
      (node (ref "IC3") (pin "6") (pinfunction "5D_6") (pintype "input"))
      (node (ref "IC5") (pin "6") (pinfunction "5D_6") (pintype "input"))
      (node (ref "IC6") (pin "6") (pinfunction "5D_6") (pintype "input"))
      (node (ref "IC8") (pin "6") (pinfunction "5D_6") (pintype "input"))
      (node (ref "IC9") (pin "6") (pinfunction "5D_6") (pintype "input"))
    )
    (net (code "6") (name "/D(F)") (class "Default")
      (node (ref "CON6") (pin "8") (pinfunction "8_8") (pintype "passive"))
      (node (ref "IC1") (pin "7") (pinfunction "6D_7") (pintype "input"))
      (node (ref "IC10") (pin "7") (pinfunction "6D_7") (pintype "input"))
      (node (ref "IC11") (pin "7") (pinfunction "6D_7") (pintype "input"))
      (node (ref "IC17") (pin "7") (pinfunction "6D_7") (pintype "input"))
      (node (ref "IC18") (pin "7") (pinfunction "6D_7") (pintype "input"))
      (node (ref "IC21") (pin "7") (pinfunction "6D_7") (pintype "input"))
      (node (ref "IC22") (pin "7") (pinfunction "6D_7") (pintype "input"))
      (node (ref "IC23") (pin "7") (pinfunction "6D_7") (pintype "input"))
      (node (ref "IC24") (pin "7") (pinfunction "6D_7") (pintype "input"))
      (node (ref "IC25") (pin "7") (pinfunction "6D_7") (pintype "input"))
      (node (ref "IC26") (pin "7") (pinfunction "6D_7") (pintype "input"))
      (node (ref "IC3") (pin "7") (pinfunction "6D_7") (pintype "input"))
      (node (ref "IC5") (pin "7") (pinfunction "6D_7") (pintype "input"))
      (node (ref "IC6") (pin "7") (pinfunction "6D_7") (pintype "input"))
      (node (ref "IC8") (pin "7") (pinfunction "6D_7") (pintype "input"))
      (node (ref "IC9") (pin "7") (pinfunction "6D_7") (pintype "input"))
    )
    (net (code "7") (name "/D(G)") (class "Default")
      (node (ref "CON6") (pin "9") (pinfunction "9_9") (pintype "passive"))
      (node (ref "IC1") (pin "8") (pinfunction "7D_8") (pintype "input"))
      (node (ref "IC10") (pin "8") (pinfunction "7D_8") (pintype "input"))
      (node (ref "IC11") (pin "8") (pinfunction "7D_8") (pintype "input"))
      (node (ref "IC17") (pin "8") (pinfunction "7D_8") (pintype "input"))
      (node (ref "IC18") (pin "8") (pinfunction "7D_8") (pintype "input"))
      (node (ref "IC21") (pin "8") (pinfunction "7D_8") (pintype "input"))
      (node (ref "IC22") (pin "8") (pinfunction "7D_8") (pintype "input"))
      (node (ref "IC23") (pin "8") (pinfunction "7D_8") (pintype "input"))
      (node (ref "IC24") (pin "8") (pinfunction "7D_8") (pintype "input"))
      (node (ref "IC25") (pin "8") (pinfunction "7D_8") (pintype "input"))
      (node (ref "IC26") (pin "8") (pinfunction "7D_8") (pintype "input"))
      (node (ref "IC3") (pin "8") (pinfunction "7D_8") (pintype "input"))
      (node (ref "IC5") (pin "8") (pinfunction "7D_8") (pintype "input"))
      (node (ref "IC6") (pin "8") (pinfunction "7D_8") (pintype "input"))
      (node (ref "IC8") (pin "8") (pinfunction "7D_8") (pintype "input"))
      (node (ref "IC9") (pin "8") (pinfunction "7D_8") (pintype "input"))
    )
    (net (code "8") (name "/D(SEL)") (class "Default")
      (node (ref "CON6") (pin "10") (pinfunction "10_10") (pintype "passive"))
      (node (ref "IC12") (pin "4") (pinfunction "I0_4") (pintype "input"))
      (node (ref "IC13") (pin "12") (pinfunction "I0_12") (pintype "input"))
      (node (ref "IC13") (pin "4") (pinfunction "I0_4") (pintype "input"))
      (node (ref "IC16") (pin "1") (pinfunction "I_1") (pintype "input"))
      (node (ref "IC16") (pin "3") (pinfunction "I_3") (pintype "input"))
      (node (ref "IC16") (pin "5") (pinfunction "I_5") (pintype "input"))
      (node (ref "IC19") (pin "4") (pinfunction "I0_4") (pintype "input"))
      (node (ref "IC2") (pin "1") (pinfunction "I_1") (pintype "input"))
      (node (ref "IC2") (pin "13") (pinfunction "I_13") (pintype "input"))
      (node (ref "IC2") (pin "3") (pinfunction "I_3") (pintype "input"))
      (node (ref "IC2") (pin "5") (pinfunction "I_5") (pintype "input"))
      (node (ref "IC2") (pin "9") (pinfunction "I_9") (pintype "input"))
      (node (ref "IC4") (pin "12") (pinfunction "I0_12") (pintype "input"))
      (node (ref "IC4") (pin "4") (pinfunction "I0_4") (pintype "input"))
      (node (ref "IC7") (pin "12") (pinfunction "I0_12") (pintype "input"))
      (node (ref "IC7") (pin "4") (pinfunction "I0_4") (pintype "input"))
    )
    (net (code "9") (name "/ICOEALU") (class "Default")
      (node (ref "CON6") (pin "22") (pinfunction "22_22") (pintype "passive"))
      (node (ref "IC19") (pin "2") (pinfunction "I1_2") (pintype "input"))
      (node (ref "IC19") (pin "5") (pinfunction "I1_5") (pintype "input"))
    )
    (net (code "10") (name "/IFL_C") (class "Default")
      (node (ref "CON6") (pin "19") (pinfunction "19_19") (pintype "passive"))
      (node (ref "R186") (pin "1") (pinfunction "1_1") (pintype "passive"))
    )
    (net (code "11") (name "/IFL_V") (class "Default")
      (node (ref "CON6") (pin "17") (pinfunction "17_17") (pintype "passive"))
      (node (ref "R184") (pin "1") (pinfunction "1_1") (pintype "passive"))
    )
    (net (code "12") (name "/IFL_Z") (class "Default")
      (node (ref "CON6") (pin "18") (pinfunction "18_18") (pintype "passive"))
      (node (ref "R185") (pin "1") (pinfunction "1_1") (pintype "passive"))
    )
    (net (code "13") (name "/ITAC") (class "Default")
      (node (ref "CON6") (pin "15") (pinfunction "15_15") (pintype "passive"))
      (node (ref "IC4") (pin "2") (pinfunction "I1_2") (pintype "input"))
      (node (ref "IC4") (pin "5") (pinfunction "I1_5") (pintype "input"))
    )
    (net (code "14") (name "/ITAR1") (class "Default")
      (node (ref "CON6") (pin "21") (pinfunction "21_21") (pintype "passive"))
      (node (ref "IC13") (pin "2") (pinfunction "I1_2") (pintype "input"))
      (node (ref "IC13") (pin "5") (pinfunction "I1_5") (pintype "input"))
    )
    (net (code "15") (name "/ITAR2") (class "Default")
      (node (ref "CON6") (pin "20") (pinfunction "20_20") (pintype "passive"))
      (node (ref "IC13") (pin "10") (pinfunction "I1_10") (pintype "input"))
      (node (ref "IC13") (pin "13") (pinfunction "I1_13") (pintype "input"))
    )
    (net (code "16") (name "/ITOP") (class "Default")
      (node (ref "CON6") (pin "11") (pinfunction "11_11") (pintype "passive"))
      (node (ref "IC12") (pin "2") (pinfunction "I1_2") (pintype "input"))
      (node (ref "IC12") (pin "5") (pinfunction "I1_5") (pintype "input"))
    )
    (net (code "17") (name "/ITRP") (class "Default")
      (node (ref "CON6") (pin "12") (pinfunction "12_12") (pintype "passive"))
    )
    (net (code "18") (name "/ITRX") (class "Default")
      (node (ref "CON6") (pin "16") (pinfunction "16_16") (pintype "passive"))
      (node (ref "IC4") (pin "10") (pinfunction "I1_10") (pintype "input"))
      (node (ref "IC4") (pin "13") (pinfunction "I1_13") (pintype "input"))
    )
    (net (code "19") (name "/ITRY") (class "Default")
      (node (ref "CON6") (pin "14") (pinfunction "14_14") (pintype "passive"))
      (node (ref "IC7") (pin "2") (pinfunction "I1_2") (pintype "input"))
      (node (ref "IC7") (pin "5") (pinfunction "I1_5") (pintype "input"))
    )
    (net (code "20") (name "/ITSP") (class "Default")
      (node (ref "CON6") (pin "13") (pinfunction "13_13") (pintype "passive"))
      (node (ref "IC7") (pin "10") (pinfunction "I1_10") (pintype "input"))
      (node (ref "IC7") (pin "13") (pinfunction "I1_13") (pintype "input"))
    )
    (net (code "21") (name "GND") (class "Default")
      (node (ref "C1") (pin "2") (pinfunction "2_2") (pintype "passive"))
      (node (ref "C10") (pin "2") (pinfunction "2_2") (pintype "passive"))
      (node (ref "C11") (pin "2") (pinfunction "2_2") (pintype "passive"))
      (node (ref "C12") (pin "2") (pinfunction "2_2") (pintype "passive"))
      (node (ref "C13") (pin "2") (pinfunction "2_2") (pintype "passive"))
      (node (ref "C14") (pin "2") (pinfunction "2_2") (pintype "passive"))
      (node (ref "C15") (pin "2") (pinfunction "2_2") (pintype "passive"))
      (node (ref "C16") (pin "2") (pinfunction "2_2") (pintype "passive"))
      (node (ref "C17") (pin "2") (pinfunction "2_2") (pintype "passive"))
      (node (ref "C18") (pin "2") (pinfunction "2_2") (pintype "passive"))
      (node (ref "C19") (pin "2") (pinfunction "2_2") (pintype "passive"))
      (node (ref "C2") (pin "2") (pinfunction "2_2") (pintype "passive"))
      (node (ref "C20") (pin "2") (pinfunction "2_2") (pintype "passive"))
      (node (ref "C21") (pin "2") (pinfunction "2_2") (pintype "passive"))
      (node (ref "C22") (pin "2") (pinfunction "2_2") (pintype "passive"))
      (node (ref "C23") (pin "2") (pinfunction "2_2") (pintype "passive"))
      (node (ref "C3") (pin "2") (pinfunction "2_2") (pintype "passive"))
      (node (ref "C4") (pin "2") (pinfunction "2_2") (pintype "passive"))
      (node (ref "C5") (pin "2") (pinfunction "2_2") (pintype "passive"))
      (node (ref "C6") (pin "2") (pinfunction "2_2") (pintype "passive"))
      (node (ref "C7") (pin "2") (pinfunction "2_2") (pintype "passive"))
      (node (ref "C8") (pin "2") (pinfunction "2_2") (pintype "passive"))
      (node (ref "C9") (pin "2") (pinfunction "2_2") (pintype "passive"))
      (node (ref "CON6") (pin "23") (pinfunction "23_23") (pintype "passive"))
      (node (ref "CON6") (pin "24") (pinfunction "24_24") (pintype "passive"))
      (node (ref "CON6") (pin "25") (pinfunction "25_25") (pintype "passive"))
      (node (ref "CON6") (pin "26") (pinfunction "26_26") (pintype "passive"))
      (node (ref "IC1") (pin "1") (pinfunction "OC_1") (pintype "input"))
      (node (ref "IC1") (pin "9") (pinfunction "8D_9") (pintype "input"))
      (node (ref "IC10") (pin "1") (pinfunction "OC_1") (pintype "input"))
      (node (ref "IC10") (pin "9") (pinfunction "8D_9") (pintype "input"))
      (node (ref "IC11") (pin "1") (pinfunction "OC_1") (pintype "input"))
      (node (ref "IC11") (pin "9") (pinfunction "8D_9") (pintype "input"))
      (node (ref "IC17") (pin "1") (pinfunction "OC_1") (pintype "input"))
      (node (ref "IC17") (pin "9") (pinfunction "8D_9") (pintype "input"))
      (node (ref "IC18") (pin "1") (pinfunction "OC_1") (pintype "input"))
      (node (ref "IC18") (pin "9") (pinfunction "8D_9") (pintype "input"))
      (node (ref "IC21") (pin "1") (pinfunction "OC_1") (pintype "input"))
      (node (ref "IC21") (pin "9") (pinfunction "8D_9") (pintype "input"))
      (node (ref "IC22") (pin "1") (pinfunction "OC_1") (pintype "input"))
      (node (ref "IC22") (pin "9") (pinfunction "8D_9") (pintype "input"))
      (node (ref "IC23") (pin "1") (pinfunction "OC_1") (pintype "input"))
      (node (ref "IC23") (pin "9") (pinfunction "8D_9") (pintype "input"))
      (node (ref "IC24") (pin "1") (pinfunction "OC_1") (pintype "input"))
      (node (ref "IC24") (pin "9") (pinfunction "8D_9") (pintype "input"))
      (node (ref "IC25") (pin "1") (pinfunction "OC_1") (pintype "input"))
      (node (ref "IC25") (pin "9") (pinfunction "8D_9") (pintype "input"))
      (node (ref "IC26") (pin "1") (pinfunction "OC_1") (pintype "input"))
      (node (ref "IC26") (pin "9") (pinfunction "8D_9") (pintype "input"))
      (node (ref "IC3") (pin "1") (pinfunction "OC_1") (pintype "input"))
      (node (ref "IC3") (pin "9") (pinfunction "8D_9") (pintype "input"))
      (node (ref "IC5") (pin "1") (pinfunction "OC_1") (pintype "input"))
      (node (ref "IC5") (pin "9") (pinfunction "8D_9") (pintype "input"))
      (node (ref "IC6") (pin "1") (pinfunction "OC_1") (pintype "input"))
      (node (ref "IC6") (pin "9") (pinfunction "8D_9") (pintype "input"))
      (node (ref "IC8") (pin "1") (pinfunction "OC_1") (pintype "input"))
      (node (ref "IC8") (pin "9") (pinfunction "8D_9") (pintype "input"))
      (node (ref "IC9") (pin "1") (pinfunction "OC_1") (pintype "input"))
      (node (ref "IC9") (pin "9") (pinfunction "8D_9") (pintype "input"))
      (node (ref "LED1") (pin "3") (pinfunction "COM_3") (pintype "passive"))
      (node (ref "LED1") (pin "8") (pinfunction "COM_8") (pintype "passive"))
      (node (ref "LED11") (pin "3") (pinfunction "COM_3") (pintype "passive"))
      (node (ref "LED11") (pin "8") (pinfunction "COM_8") (pintype "passive"))
      (node (ref "LED12") (pin "3") (pinfunction "COM_3") (pintype "passive"))
      (node (ref "LED12") (pin "8") (pinfunction "COM_8") (pintype "passive"))
      (node (ref "LED13") (pin "3") (pinfunction "COM_3") (pintype "passive"))
      (node (ref "LED13") (pin "8") (pinfunction "COM_8") (pintype "passive"))
      (node (ref "LED14") (pin "3") (pinfunction "COM_3") (pintype "passive"))
      (node (ref "LED14") (pin "8") (pinfunction "COM_8") (pintype "passive"))
      (node (ref "LED15") (pin "3") (pinfunction "COM_3") (pintype "passive"))
      (node (ref "LED15") (pin "8") (pinfunction "COM_8") (pintype "passive"))
      (node (ref "LED16") (pin "3") (pinfunction "COM_3") (pintype "passive"))
      (node (ref "LED16") (pin "8") (pinfunction "COM_8") (pintype "passive"))
      (node (ref "LED17") (pin "3") (pinfunction "COM_3") (pintype "passive"))
      (node (ref "LED17") (pin "8") (pinfunction "COM_8") (pintype "passive"))
      (node (ref "LED18") (pin "3") (pinfunction "COM_3") (pintype "passive"))
      (node (ref "LED18") (pin "8") (pinfunction "COM_8") (pintype "passive"))
      (node (ref "LED2") (pin "3") (pinfunction "COM_3") (pintype "passive"))
      (node (ref "LED2") (pin "8") (pinfunction "COM_8") (pintype "passive"))
      (node (ref "LED28") (pin "K") (pinfunction "C_K") (pintype "passive"))
      (node (ref "LED29") (pin "K") (pinfunction "C_K") (pintype "passive"))
      (node (ref "LED3") (pin "3") (pinfunction "COM_3") (pintype "passive"))
      (node (ref "LED3") (pin "8") (pinfunction "COM_8") (pintype "passive"))
      (node (ref "LED30") (pin "K") (pinfunction "C_K") (pintype "passive"))
      (node (ref "LED4") (pin "3") (pinfunction "COM_3") (pintype "passive"))
      (node (ref "LED4") (pin "8") (pinfunction "COM_8") (pintype "passive"))
      (node (ref "LED5") (pin "3") (pinfunction "COM_3") (pintype "passive"))
      (node (ref "LED5") (pin "8") (pinfunction "COM_8") (pintype "passive"))
      (node (ref "LED6") (pin "3") (pinfunction "COM_3") (pintype "passive"))
      (node (ref "LED6") (pin "8") (pinfunction "COM_8") (pintype "passive"))
      (node (ref "LED7") (pin "3") (pinfunction "COM_3") (pintype "passive"))
      (node (ref "LED7") (pin "8") (pinfunction "COM_8") (pintype "passive"))
      (node (ref "LED8") (pin "3") (pinfunction "COM_3") (pintype "passive"))
      (node (ref "LED8") (pin "8") (pinfunction "COM_8") (pintype "passive"))
    )
    (net (code "22") (name "Net-(IC1A-1Q)") (class "Default")
      (node (ref "IC1") (pin "19") (pinfunction "1Q_19") (pintype "tri_state"))
      (node (ref "R1") (pin "1") (pinfunction "1_1") (pintype "passive"))
    )
    (net (code "23") (name "Net-(IC1A-2Q)") (class "Default")
      (node (ref "IC1") (pin "18") (pinfunction "2Q_18") (pintype "tri_state"))
      (node (ref "R2") (pin "1") (pinfunction "1_1") (pintype "passive"))
    )
    (net (code "24") (name "Net-(IC1A-3Q)") (class "Default")
      (node (ref "IC1") (pin "17") (pinfunction "3Q_17") (pintype "tri_state"))
      (node (ref "R3") (pin "1") (pinfunction "1_1") (pintype "passive"))
    )
    (net (code "25") (name "Net-(IC1A-4Q)") (class "Default")
      (node (ref "IC1") (pin "16") (pinfunction "4Q_16") (pintype "tri_state"))
      (node (ref "R4") (pin "1") (pinfunction "1_1") (pintype "passive"))
    )
    (net (code "26") (name "Net-(IC1A-5Q)") (class "Default")
      (node (ref "IC1") (pin "15") (pinfunction "5Q_15") (pintype "tri_state"))
      (node (ref "R5") (pin "1") (pinfunction "1_1") (pintype "passive"))
    )
    (net (code "27") (name "Net-(IC1A-6Q)") (class "Default")
      (node (ref "IC1") (pin "14") (pinfunction "6Q_14") (pintype "tri_state"))
      (node (ref "R6") (pin "1") (pinfunction "1_1") (pintype "passive"))
    )
    (net (code "28") (name "Net-(IC1A-7Q)") (class "Default")
      (node (ref "IC1") (pin "13") (pinfunction "7Q_13") (pintype "tri_state"))
      (node (ref "R7") (pin "1") (pinfunction "1_1") (pintype "passive"))
    )
    (net (code "29") (name "Net-(IC1A-CLK)") (class "Default")
      (node (ref "IC1") (pin "11") (pinfunction "CLK_11") (pintype "input"))
      (node (ref "IC4") (pin "3") (pinfunction "O_3") (pintype "output"))
    )
    (net (code "30") (name "Net-(IC2A-O)") (class "Default")
      (node (ref "IC2") (pin "2") (pinfunction "O_2") (pintype "output"))
      (node (ref "IC4") (pin "1") (pinfunction "I0_1") (pintype "input"))
    )
    (net (code "31") (name "Net-(IC2B-O)") (class "Default")
      (node (ref "IC2") (pin "4") (pinfunction "O_4") (pintype "output"))
      (node (ref "IC4") (pin "9") (pinfunction "I0_9") (pintype "input"))
    )
    (net (code "32") (name "Net-(IC2C-O)") (class "Default")
      (node (ref "IC2") (pin "6") (pinfunction "O_6") (pintype "output"))
      (node (ref "IC7") (pin "1") (pinfunction "I0_1") (pintype "input"))
    )
    (net (code "33") (name "Net-(IC2D-O)") (class "Default")
      (node (ref "IC2") (pin "8") (pinfunction "O_8") (pintype "output"))
      (node (ref "IC7") (pin "9") (pinfunction "I0_9") (pintype "input"))
    )
    (net (code "34") (name "Net-(IC3A-1Q)") (class "Default")
      (node (ref "IC3") (pin "19") (pinfunction "1Q_19") (pintype "tri_state"))
      (node (ref "R8") (pin "1") (pinfunction "1_1") (pintype "passive"))
    )
    (net (code "35") (name "Net-(IC3A-2Q)") (class "Default")
      (node (ref "IC3") (pin "18") (pinfunction "2Q_18") (pintype "tri_state"))
      (node (ref "R9") (pin "1") (pinfunction "1_1") (pintype "passive"))
    )
    (net (code "36") (name "Net-(IC3A-3Q)") (class "Default")
      (node (ref "IC3") (pin "17") (pinfunction "3Q_17") (pintype "tri_state"))
      (node (ref "R10") (pin "1") (pinfunction "1_1") (pintype "passive"))
    )
    (net (code "37") (name "Net-(IC3A-4Q)") (class "Default")
      (node (ref "IC3") (pin "16") (pinfunction "4Q_16") (pintype "tri_state"))
      (node (ref "R11") (pin "1") (pinfunction "1_1") (pintype "passive"))
    )
    (net (code "38") (name "Net-(IC3A-5Q)") (class "Default")
      (node (ref "IC3") (pin "15") (pinfunction "5Q_15") (pintype "tri_state"))
      (node (ref "R12") (pin "1") (pinfunction "1_1") (pintype "passive"))
    )
    (net (code "39") (name "Net-(IC3A-6Q)") (class "Default")
      (node (ref "IC3") (pin "14") (pinfunction "6Q_14") (pintype "tri_state"))
      (node (ref "R13") (pin "1") (pinfunction "1_1") (pintype "passive"))
    )
    (net (code "40") (name "Net-(IC3A-7Q)") (class "Default")
      (node (ref "IC3") (pin "13") (pinfunction "7Q_13") (pintype "tri_state"))
      (node (ref "R14") (pin "1") (pinfunction "1_1") (pintype "passive"))
    )
    (net (code "41") (name "Net-(IC3A-CLK)") (class "Default")
      (node (ref "IC3") (pin "11") (pinfunction "CLK_11") (pintype "input"))
      (node (ref "IC4") (pin "6") (pinfunction "O_6") (pintype "output"))
    )
    (net (code "42") (name "Net-(IC4C-O)") (class "Default")
      (node (ref "IC4") (pin "8") (pinfunction "O_8") (pintype "output"))
      (node (ref "IC5") (pin "11") (pinfunction "CLK_11") (pintype "input"))
    )
    (net (code "43") (name "Net-(IC4D-O)") (class "Default")
      (node (ref "IC4") (pin "11") (pinfunction "O_11") (pintype "output"))
      (node (ref "IC6") (pin "11") (pinfunction "CLK_11") (pintype "input"))
    )
    (net (code "44") (name "Net-(IC5A-1Q)") (class "Default")
      (node (ref "IC5") (pin "19") (pinfunction "1Q_19") (pintype "tri_state"))
      (node (ref "R15") (pin "1") (pinfunction "1_1") (pintype "passive"))
    )
    (net (code "45") (name "Net-(IC5A-2Q)") (class "Default")
      (node (ref "IC5") (pin "18") (pinfunction "2Q_18") (pintype "tri_state"))
      (node (ref "R16") (pin "1") (pinfunction "1_1") (pintype "passive"))
    )
    (net (code "46") (name "Net-(IC5A-3Q)") (class "Default")
      (node (ref "IC5") (pin "17") (pinfunction "3Q_17") (pintype "tri_state"))
      (node (ref "R17") (pin "1") (pinfunction "1_1") (pintype "passive"))
    )
    (net (code "47") (name "Net-(IC5A-4Q)") (class "Default")
      (node (ref "IC5") (pin "16") (pinfunction "4Q_16") (pintype "tri_state"))
      (node (ref "R18") (pin "1") (pinfunction "1_1") (pintype "passive"))
    )
    (net (code "48") (name "Net-(IC5A-5Q)") (class "Default")
      (node (ref "IC5") (pin "15") (pinfunction "5Q_15") (pintype "tri_state"))
      (node (ref "R19") (pin "1") (pinfunction "1_1") (pintype "passive"))
    )
    (net (code "49") (name "Net-(IC5A-6Q)") (class "Default")
      (node (ref "IC5") (pin "14") (pinfunction "6Q_14") (pintype "tri_state"))
      (node (ref "R20") (pin "1") (pinfunction "1_1") (pintype "passive"))
    )
    (net (code "50") (name "Net-(IC5A-7Q)") (class "Default")
      (node (ref "IC5") (pin "13") (pinfunction "7Q_13") (pintype "tri_state"))
      (node (ref "R21") (pin "1") (pinfunction "1_1") (pintype "passive"))
    )
    (net (code "51") (name "Net-(IC6A-1Q)") (class "Default")
      (node (ref "IC6") (pin "19") (pinfunction "1Q_19") (pintype "tri_state"))
      (node (ref "R22") (pin "1") (pinfunction "1_1") (pintype "passive"))
    )
    (net (code "52") (name "Net-(IC6A-2Q)") (class "Default")
      (node (ref "IC6") (pin "18") (pinfunction "2Q_18") (pintype "tri_state"))
      (node (ref "R23") (pin "1") (pinfunction "1_1") (pintype "passive"))
    )
    (net (code "53") (name "Net-(IC6A-3Q)") (class "Default")
      (node (ref "IC6") (pin "17") (pinfunction "3Q_17") (pintype "tri_state"))
      (node (ref "R24") (pin "1") (pinfunction "1_1") (pintype "passive"))
    )
    (net (code "54") (name "Net-(IC6A-4Q)") (class "Default")
      (node (ref "IC6") (pin "16") (pinfunction "4Q_16") (pintype "tri_state"))
      (node (ref "R25") (pin "1") (pinfunction "1_1") (pintype "passive"))
    )
    (net (code "55") (name "Net-(IC6A-5Q)") (class "Default")
      (node (ref "IC6") (pin "15") (pinfunction "5Q_15") (pintype "tri_state"))
      (node (ref "R26") (pin "1") (pinfunction "1_1") (pintype "passive"))
    )
    (net (code "56") (name "Net-(IC6A-6Q)") (class "Default")
      (node (ref "IC6") (pin "14") (pinfunction "6Q_14") (pintype "tri_state"))
      (node (ref "R27") (pin "1") (pinfunction "1_1") (pintype "passive"))
    )
    (net (code "57") (name "Net-(IC6A-7Q)") (class "Default")
      (node (ref "IC6") (pin "13") (pinfunction "7Q_13") (pintype "tri_state"))
      (node (ref "R28") (pin "1") (pinfunction "1_1") (pintype "passive"))
    )
    (net (code "58") (name "Net-(IC7C-O)") (class "Default")
      (node (ref "IC7") (pin "8") (pinfunction "O_8") (pintype "output"))
      (node (ref "IC8") (pin "11") (pinfunction "CLK_11") (pintype "input"))
    )
    (net (code "59") (name "Net-(IC7D-O)") (class "Default")
      (node (ref "IC7") (pin "11") (pinfunction "O_11") (pintype "output"))
      (node (ref "IC9") (pin "11") (pinfunction "CLK_11") (pintype "input"))
    )
    (net (code "60") (name "Net-(IC8A-1Q)") (class "Default")
      (node (ref "IC8") (pin "19") (pinfunction "1Q_19") (pintype "tri_state"))
      (node (ref "R43") (pin "1") (pinfunction "1_1") (pintype "passive"))
    )
    (net (code "61") (name "Net-(IC8A-2Q)") (class "Default")
      (node (ref "IC8") (pin "18") (pinfunction "2Q_18") (pintype "tri_state"))
      (node (ref "R44") (pin "1") (pinfunction "1_1") (pintype "passive"))
    )
    (net (code "62") (name "Net-(IC8A-3Q)") (class "Default")
      (node (ref "IC8") (pin "17") (pinfunction "3Q_17") (pintype "tri_state"))
      (node (ref "R45") (pin "1") (pinfunction "1_1") (pintype "passive"))
    )
    (net (code "63") (name "Net-(IC8A-4Q)") (class "Default")
      (node (ref "IC8") (pin "16") (pinfunction "4Q_16") (pintype "tri_state"))
      (node (ref "R46") (pin "1") (pinfunction "1_1") (pintype "passive"))
    )
    (net (code "64") (name "Net-(IC8A-5Q)") (class "Default")
      (node (ref "IC8") (pin "15") (pinfunction "5Q_15") (pintype "tri_state"))
      (node (ref "R47") (pin "1") (pinfunction "1_1") (pintype "passive"))
    )
    (net (code "65") (name "Net-(IC8A-6Q)") (class "Default")
      (node (ref "IC8") (pin "14") (pinfunction "6Q_14") (pintype "tri_state"))
      (node (ref "R48") (pin "1") (pinfunction "1_1") (pintype "passive"))
    )
    (net (code "66") (name "Net-(IC8A-7Q)") (class "Default")
      (node (ref "IC8") (pin "13") (pinfunction "7Q_13") (pintype "tri_state"))
      (node (ref "R49") (pin "1") (pinfunction "1_1") (pintype "passive"))
    )
    (net (code "67") (name "Net-(IC9A-1Q)") (class "Default")
      (node (ref "IC9") (pin "19") (pinfunction "1Q_19") (pintype "tri_state"))
      (node (ref "R50") (pin "1") (pinfunction "1_1") (pintype "passive"))
    )
    (net (code "68") (name "Net-(IC9A-2Q)") (class "Default")
      (node (ref "IC9") (pin "18") (pinfunction "2Q_18") (pintype "tri_state"))
      (node (ref "R51") (pin "1") (pinfunction "1_1") (pintype "passive"))
    )
    (net (code "69") (name "Net-(IC9A-3Q)") (class "Default")
      (node (ref "IC9") (pin "17") (pinfunction "3Q_17") (pintype "tri_state"))
      (node (ref "R52") (pin "1") (pinfunction "1_1") (pintype "passive"))
    )
    (net (code "70") (name "Net-(IC9A-4Q)") (class "Default")
      (node (ref "IC9") (pin "16") (pinfunction "4Q_16") (pintype "tri_state"))
      (node (ref "R53") (pin "1") (pinfunction "1_1") (pintype "passive"))
    )
    (net (code "71") (name "Net-(IC9A-5Q)") (class "Default")
      (node (ref "IC9") (pin "15") (pinfunction "5Q_15") (pintype "tri_state"))
      (node (ref "R54") (pin "1") (pinfunction "1_1") (pintype "passive"))
    )
    (net (code "72") (name "Net-(IC9A-6Q)") (class "Default")
      (node (ref "IC9") (pin "14") (pinfunction "6Q_14") (pintype "tri_state"))
      (node (ref "R55") (pin "1") (pinfunction "1_1") (pintype "passive"))
    )
    (net (code "73") (name "Net-(IC9A-7Q)") (class "Default")
      (node (ref "IC9") (pin "13") (pinfunction "7Q_13") (pintype "tri_state"))
      (node (ref "R56") (pin "1") (pinfunction "1_1") (pintype "passive"))
    )
    (net (code "74") (name "Net-(IC10A-1Q)") (class "Default")
      (node (ref "IC10") (pin "19") (pinfunction "1Q_19") (pintype "tri_state"))
      (node (ref "R29") (pin "1") (pinfunction "1_1") (pintype "passive"))
    )
    (net (code "75") (name "Net-(IC10A-2Q)") (class "Default")
      (node (ref "IC10") (pin "18") (pinfunction "2Q_18") (pintype "tri_state"))
      (node (ref "R30") (pin "1") (pinfunction "1_1") (pintype "passive"))
    )
    (net (code "76") (name "Net-(IC10A-3Q)") (class "Default")
      (node (ref "IC10") (pin "17") (pinfunction "3Q_17") (pintype "tri_state"))
      (node (ref "R31") (pin "1") (pinfunction "1_1") (pintype "passive"))
    )
    (net (code "77") (name "Net-(IC10A-4Q)") (class "Default")
      (node (ref "IC10") (pin "16") (pinfunction "4Q_16") (pintype "tri_state"))
      (node (ref "R32") (pin "1") (pinfunction "1_1") (pintype "passive"))
    )
    (net (code "78") (name "Net-(IC10A-5Q)") (class "Default")
      (node (ref "IC10") (pin "15") (pinfunction "5Q_15") (pintype "tri_state"))
      (node (ref "R33") (pin "1") (pinfunction "1_1") (pintype "passive"))
    )
    (net (code "79") (name "Net-(IC10A-6Q)") (class "Default")
      (node (ref "IC10") (pin "14") (pinfunction "6Q_14") (pintype "tri_state"))
      (node (ref "R34") (pin "1") (pinfunction "1_1") (pintype "passive"))
    )
    (net (code "80") (name "Net-(IC10A-7Q)") (class "Default")
      (node (ref "IC10") (pin "13") (pinfunction "7Q_13") (pintype "tri_state"))
      (node (ref "R35") (pin "1") (pinfunction "1_1") (pintype "passive"))
    )
    (net (code "81") (name "Net-(IC10A-CLK)") (class "Default")
      (node (ref "IC10") (pin "11") (pinfunction "CLK_11") (pintype "input"))
      (node (ref "IC7") (pin "3") (pinfunction "O_3") (pintype "output"))
    )
    (net (code "82") (name "Net-(IC11A-1Q)") (class "Default")
      (node (ref "IC11") (pin "19") (pinfunction "1Q_19") (pintype "tri_state"))
      (node (ref "R36") (pin "1") (pinfunction "1_1") (pintype "passive"))
    )
    (net (code "83") (name "Net-(IC11A-2Q)") (class "Default")
      (node (ref "IC11") (pin "18") (pinfunction "2Q_18") (pintype "tri_state"))
      (node (ref "R37") (pin "1") (pinfunction "1_1") (pintype "passive"))
    )
    (net (code "84") (name "Net-(IC11A-3Q)") (class "Default")
      (node (ref "IC11") (pin "17") (pinfunction "3Q_17") (pintype "tri_state"))
      (node (ref "R38") (pin "1") (pinfunction "1_1") (pintype "passive"))
    )
    (net (code "85") (name "Net-(IC11A-4Q)") (class "Default")
      (node (ref "IC11") (pin "16") (pinfunction "4Q_16") (pintype "tri_state"))
      (node (ref "R39") (pin "1") (pinfunction "1_1") (pintype "passive"))
    )
    (net (code "86") (name "Net-(IC11A-5Q)") (class "Default")
      (node (ref "IC11") (pin "15") (pinfunction "5Q_15") (pintype "tri_state"))
      (node (ref "R40") (pin "1") (pinfunction "1_1") (pintype "passive"))
    )
    (net (code "87") (name "Net-(IC11A-6Q)") (class "Default")
      (node (ref "IC11") (pin "14") (pinfunction "6Q_14") (pintype "tri_state"))
      (node (ref "R41") (pin "1") (pinfunction "1_1") (pintype "passive"))
    )
    (net (code "88") (name "Net-(IC11A-7Q)") (class "Default")
      (node (ref "IC11") (pin "13") (pinfunction "7Q_13") (pintype "tri_state"))
      (node (ref "R42") (pin "1") (pinfunction "1_1") (pintype "passive"))
    )
    (net (code "89") (name "Net-(IC11A-CLK)") (class "Default")
      (node (ref "IC11") (pin "11") (pinfunction "CLK_11") (pintype "input"))
      (node (ref "IC7") (pin "6") (pinfunction "O_6") (pintype "output"))
    )
    (net (code "90") (name "Net-(IC12A-I0)") (class "Default")
      (node (ref "IC12") (pin "1") (pinfunction "I0_1") (pintype "input"))
      (node (ref "IC2") (pin "12") (pinfunction "O_12") (pintype "output"))
    )
    (net (code "91") (name "Net-(IC12A-O)") (class "Default")
      (node (ref "IC12") (pin "3") (pinfunction "O_3") (pintype "output"))
      (node (ref "IC17") (pin "11") (pinfunction "CLK_11") (pintype "input"))
    )
    (net (code "92") (name "Net-(IC12B-O)") (class "Default")
      (node (ref "IC12") (pin "6") (pinfunction "O_6") (pintype "output"))
      (node (ref "IC18") (pin "11") (pinfunction "CLK_11") (pintype "input"))
    )
    (net (code "93") (name "Net-(IC13A-I0)") (class "Default")
      (node (ref "IC13") (pin "1") (pinfunction "I0_1") (pintype "input"))
      (node (ref "IC16") (pin "2") (pinfunction "O_2") (pintype "output"))
    )
    (net (code "94") (name "Net-(IC13A-O)") (class "Default")
      (node (ref "IC13") (pin "3") (pinfunction "O_3") (pintype "output"))
      (node (ref "IC21") (pin "11") (pinfunction "CLK_11") (pintype "input"))
    )
    (net (code "95") (name "Net-(IC13B-O)") (class "Default")
      (node (ref "IC13") (pin "6") (pinfunction "O_6") (pintype "output"))
      (node (ref "IC22") (pin "11") (pinfunction "CLK_11") (pintype "input"))
    )
    (net (code "96") (name "Net-(IC13C-I0)") (class "Default")
      (node (ref "IC13") (pin "9") (pinfunction "I0_9") (pintype "input"))
      (node (ref "IC16") (pin "4") (pinfunction "O_4") (pintype "output"))
    )
    (net (code "97") (name "Net-(IC13C-O)") (class "Default")
      (node (ref "IC13") (pin "8") (pinfunction "O_8") (pintype "output"))
      (node (ref "IC23") (pin "11") (pinfunction "CLK_11") (pintype "input"))
    )
    (net (code "98") (name "Net-(IC13D-O)") (class "Default")
      (node (ref "IC13") (pin "11") (pinfunction "O_11") (pintype "output"))
      (node (ref "IC24") (pin "11") (pinfunction "CLK_11") (pintype "input"))
    )
    (net (code "99") (name "Net-(IC16C-O)") (class "Default")
      (node (ref "IC16") (pin "6") (pinfunction "O_6") (pintype "output"))
      (node (ref "IC19") (pin "1") (pinfunction "I0_1") (pintype "input"))
    )
    (net (code "100") (name "Net-(IC17A-1Q)") (class "Default")
      (node (ref "IC17") (pin "19") (pinfunction "1Q_19") (pintype "tri_state"))
      (node (ref "R71") (pin "1") (pinfunction "1_1") (pintype "passive"))
    )
    (net (code "101") (name "Net-(IC17A-2Q)") (class "Default")
      (node (ref "IC17") (pin "18") (pinfunction "2Q_18") (pintype "tri_state"))
      (node (ref "R72") (pin "1") (pinfunction "1_1") (pintype "passive"))
    )
    (net (code "102") (name "Net-(IC17A-3Q)") (class "Default")
      (node (ref "IC17") (pin "17") (pinfunction "3Q_17") (pintype "tri_state"))
      (node (ref "R73") (pin "1") (pinfunction "1_1") (pintype "passive"))
    )
    (net (code "103") (name "Net-(IC17A-4Q)") (class "Default")
      (node (ref "IC17") (pin "16") (pinfunction "4Q_16") (pintype "tri_state"))
      (node (ref "R74") (pin "1") (pinfunction "1_1") (pintype "passive"))
    )
    (net (code "104") (name "Net-(IC17A-5Q)") (class "Default")
      (node (ref "IC17") (pin "15") (pinfunction "5Q_15") (pintype "tri_state"))
      (node (ref "R75") (pin "1") (pinfunction "1_1") (pintype "passive"))
    )
    (net (code "105") (name "Net-(IC17A-6Q)") (class "Default")
      (node (ref "IC17") (pin "14") (pinfunction "6Q_14") (pintype "tri_state"))
      (node (ref "R76") (pin "1") (pinfunction "1_1") (pintype "passive"))
    )
    (net (code "106") (name "Net-(IC17A-7Q)") (class "Default")
      (node (ref "IC17") (pin "13") (pinfunction "7Q_13") (pintype "tri_state"))
      (node (ref "R77") (pin "1") (pinfunction "1_1") (pintype "passive"))
    )
    (net (code "107") (name "Net-(IC18A-1Q)") (class "Default")
      (node (ref "IC18") (pin "19") (pinfunction "1Q_19") (pintype "tri_state"))
      (node (ref "R78") (pin "1") (pinfunction "1_1") (pintype "passive"))
    )
    (net (code "108") (name "Net-(IC18A-2Q)") (class "Default")
      (node (ref "IC18") (pin "18") (pinfunction "2Q_18") (pintype "tri_state"))
      (node (ref "R79") (pin "1") (pinfunction "1_1") (pintype "passive"))
    )
    (net (code "109") (name "Net-(IC18A-3Q)") (class "Default")
      (node (ref "IC18") (pin "17") (pinfunction "3Q_17") (pintype "tri_state"))
      (node (ref "R80") (pin "1") (pinfunction "1_1") (pintype "passive"))
    )
    (net (code "110") (name "Net-(IC18A-4Q)") (class "Default")
      (node (ref "IC18") (pin "16") (pinfunction "4Q_16") (pintype "tri_state"))
      (node (ref "R81") (pin "1") (pinfunction "1_1") (pintype "passive"))
    )
    (net (code "111") (name "Net-(IC18A-5Q)") (class "Default")
      (node (ref "IC18") (pin "15") (pinfunction "5Q_15") (pintype "tri_state"))
      (node (ref "R82") (pin "1") (pinfunction "1_1") (pintype "passive"))
    )
    (net (code "112") (name "Net-(IC18A-6Q)") (class "Default")
      (node (ref "IC18") (pin "14") (pinfunction "6Q_14") (pintype "tri_state"))
      (node (ref "R83") (pin "1") (pinfunction "1_1") (pintype "passive"))
    )
    (net (code "113") (name "Net-(IC18A-7Q)") (class "Default")
      (node (ref "IC18") (pin "13") (pinfunction "7Q_13") (pintype "tri_state"))
      (node (ref "R84") (pin "1") (pinfunction "1_1") (pintype "passive"))
    )
    (net (code "114") (name "Net-(IC19A-O)") (class "Default")
      (node (ref "IC19") (pin "3") (pinfunction "O_3") (pintype "output"))
      (node (ref "IC25") (pin "11") (pinfunction "CLK_11") (pintype "input"))
    )
    (net (code "115") (name "Net-(IC19B-O)") (class "Default")
      (node (ref "IC19") (pin "6") (pinfunction "O_6") (pintype "output"))
      (node (ref "IC26") (pin "11") (pinfunction "CLK_11") (pintype "input"))
    )
    (net (code "116") (name "Net-(IC21A-1Q)") (class "Default")
      (node (ref "IC21") (pin "19") (pinfunction "1Q_19") (pintype "tri_state"))
      (node (ref "R85") (pin "1") (pinfunction "1_1") (pintype "passive"))
    )
    (net (code "117") (name "Net-(IC21A-2Q)") (class "Default")
      (node (ref "IC21") (pin "18") (pinfunction "2Q_18") (pintype "tri_state"))
      (node (ref "R86") (pin "1") (pinfunction "1_1") (pintype "passive"))
    )
    (net (code "118") (name "Net-(IC21A-3Q)") (class "Default")
      (node (ref "IC21") (pin "17") (pinfunction "3Q_17") (pintype "tri_state"))
      (node (ref "R87") (pin "1") (pinfunction "1_1") (pintype "passive"))
    )
    (net (code "119") (name "Net-(IC21A-4Q)") (class "Default")
      (node (ref "IC21") (pin "16") (pinfunction "4Q_16") (pintype "tri_state"))
      (node (ref "R88") (pin "1") (pinfunction "1_1") (pintype "passive"))
    )
    (net (code "120") (name "Net-(IC21A-5Q)") (class "Default")
      (node (ref "IC21") (pin "15") (pinfunction "5Q_15") (pintype "tri_state"))
      (node (ref "R89") (pin "1") (pinfunction "1_1") (pintype "passive"))
    )
    (net (code "121") (name "Net-(IC21A-6Q)") (class "Default")
      (node (ref "IC21") (pin "14") (pinfunction "6Q_14") (pintype "tri_state"))
      (node (ref "R90") (pin "1") (pinfunction "1_1") (pintype "passive"))
    )
    (net (code "122") (name "Net-(IC21A-7Q)") (class "Default")
      (node (ref "IC21") (pin "13") (pinfunction "7Q_13") (pintype "tri_state"))
      (node (ref "R91") (pin "1") (pinfunction "1_1") (pintype "passive"))
    )
    (net (code "123") (name "Net-(IC22A-1Q)") (class "Default")
      (node (ref "IC22") (pin "19") (pinfunction "1Q_19") (pintype "tri_state"))
      (node (ref "R92") (pin "1") (pinfunction "1_1") (pintype "passive"))
    )
    (net (code "124") (name "Net-(IC22A-2Q)") (class "Default")
      (node (ref "IC22") (pin "18") (pinfunction "2Q_18") (pintype "tri_state"))
      (node (ref "R93") (pin "1") (pinfunction "1_1") (pintype "passive"))
    )
    (net (code "125") (name "Net-(IC22A-3Q)") (class "Default")
      (node (ref "IC22") (pin "17") (pinfunction "3Q_17") (pintype "tri_state"))
      (node (ref "R94") (pin "1") (pinfunction "1_1") (pintype "passive"))
    )
    (net (code "126") (name "Net-(IC22A-4Q)") (class "Default")
      (node (ref "IC22") (pin "16") (pinfunction "4Q_16") (pintype "tri_state"))
      (node (ref "R95") (pin "1") (pinfunction "1_1") (pintype "passive"))
    )
    (net (code "127") (name "Net-(IC22A-5Q)") (class "Default")
      (node (ref "IC22") (pin "15") (pinfunction "5Q_15") (pintype "tri_state"))
      (node (ref "R96") (pin "1") (pinfunction "1_1") (pintype "passive"))
    )
    (net (code "128") (name "Net-(IC22A-6Q)") (class "Default")
      (node (ref "IC22") (pin "14") (pinfunction "6Q_14") (pintype "tri_state"))
      (node (ref "R97") (pin "1") (pinfunction "1_1") (pintype "passive"))
    )
    (net (code "129") (name "Net-(IC22A-7Q)") (class "Default")
      (node (ref "IC22") (pin "13") (pinfunction "7Q_13") (pintype "tri_state"))
      (node (ref "R98") (pin "1") (pinfunction "1_1") (pintype "passive"))
    )
    (net (code "130") (name "Net-(IC23A-1Q)") (class "Default")
      (node (ref "IC23") (pin "19") (pinfunction "1Q_19") (pintype "tri_state"))
      (node (ref "R99") (pin "1") (pinfunction "1_1") (pintype "passive"))
    )
    (net (code "131") (name "Net-(IC23A-2Q)") (class "Default")
      (node (ref "IC23") (pin "18") (pinfunction "2Q_18") (pintype "tri_state"))
      (node (ref "R100") (pin "1") (pinfunction "1_1") (pintype "passive"))
    )
    (net (code "132") (name "Net-(IC23A-3Q)") (class "Default")
      (node (ref "IC23") (pin "17") (pinfunction "3Q_17") (pintype "tri_state"))
      (node (ref "R101") (pin "1") (pinfunction "1_1") (pintype "passive"))
    )
    (net (code "133") (name "Net-(IC23A-4Q)") (class "Default")
      (node (ref "IC23") (pin "16") (pinfunction "4Q_16") (pintype "tri_state"))
      (node (ref "R102") (pin "1") (pinfunction "1_1") (pintype "passive"))
    )
    (net (code "134") (name "Net-(IC23A-5Q)") (class "Default")
      (node (ref "IC23") (pin "15") (pinfunction "5Q_15") (pintype "tri_state"))
      (node (ref "R103") (pin "1") (pinfunction "1_1") (pintype "passive"))
    )
    (net (code "135") (name "Net-(IC23A-6Q)") (class "Default")
      (node (ref "IC23") (pin "14") (pinfunction "6Q_14") (pintype "tri_state"))
      (node (ref "R104") (pin "1") (pinfunction "1_1") (pintype "passive"))
    )
    (net (code "136") (name "Net-(IC23A-7Q)") (class "Default")
      (node (ref "IC23") (pin "13") (pinfunction "7Q_13") (pintype "tri_state"))
      (node (ref "R105") (pin "1") (pinfunction "1_1") (pintype "passive"))
    )
    (net (code "137") (name "Net-(IC24A-1Q)") (class "Default")
      (node (ref "IC24") (pin "19") (pinfunction "1Q_19") (pintype "tri_state"))
      (node (ref "R106") (pin "1") (pinfunction "1_1") (pintype "passive"))
    )
    (net (code "138") (name "Net-(IC24A-2Q)") (class "Default")
      (node (ref "IC24") (pin "18") (pinfunction "2Q_18") (pintype "tri_state"))
      (node (ref "R107") (pin "1") (pinfunction "1_1") (pintype "passive"))
    )
    (net (code "139") (name "Net-(IC24A-3Q)") (class "Default")
      (node (ref "IC24") (pin "17") (pinfunction "3Q_17") (pintype "tri_state"))
      (node (ref "R108") (pin "1") (pinfunction "1_1") (pintype "passive"))
    )
    (net (code "140") (name "Net-(IC24A-4Q)") (class "Default")
      (node (ref "IC24") (pin "16") (pinfunction "4Q_16") (pintype "tri_state"))
      (node (ref "R109") (pin "1") (pinfunction "1_1") (pintype "passive"))
    )
    (net (code "141") (name "Net-(IC24A-5Q)") (class "Default")
      (node (ref "IC24") (pin "15") (pinfunction "5Q_15") (pintype "tri_state"))
      (node (ref "R110") (pin "1") (pinfunction "1_1") (pintype "passive"))
    )
    (net (code "142") (name "Net-(IC24A-6Q)") (class "Default")
      (node (ref "IC24") (pin "14") (pinfunction "6Q_14") (pintype "tri_state"))
      (node (ref "R111") (pin "1") (pinfunction "1_1") (pintype "passive"))
    )
    (net (code "143") (name "Net-(IC24A-7Q)") (class "Default")
      (node (ref "IC24") (pin "13") (pinfunction "7Q_13") (pintype "tri_state"))
      (node (ref "R112") (pin "1") (pinfunction "1_1") (pintype "passive"))
    )
    (net (code "144") (name "Net-(IC25A-1Q)") (class "Default")
      (node (ref "IC25") (pin "19") (pinfunction "1Q_19") (pintype "tri_state"))
      (node (ref "R113") (pin "1") (pinfunction "1_1") (pintype "passive"))
    )
    (net (code "145") (name "Net-(IC25A-2Q)") (class "Default")
      (node (ref "IC25") (pin "18") (pinfunction "2Q_18") (pintype "tri_state"))
      (node (ref "R114") (pin "1") (pinfunction "1_1") (pintype "passive"))
    )
    (net (code "146") (name "Net-(IC25A-3Q)") (class "Default")
      (node (ref "IC25") (pin "17") (pinfunction "3Q_17") (pintype "tri_state"))
      (node (ref "R115") (pin "1") (pinfunction "1_1") (pintype "passive"))
    )
    (net (code "147") (name "Net-(IC25A-4Q)") (class "Default")
      (node (ref "IC25") (pin "16") (pinfunction "4Q_16") (pintype "tri_state"))
      (node (ref "R116") (pin "1") (pinfunction "1_1") (pintype "passive"))
    )
    (net (code "148") (name "Net-(IC25A-5Q)") (class "Default")
      (node (ref "IC25") (pin "15") (pinfunction "5Q_15") (pintype "tri_state"))
      (node (ref "R117") (pin "1") (pinfunction "1_1") (pintype "passive"))
    )
    (net (code "149") (name "Net-(IC25A-6Q)") (class "Default")
      (node (ref "IC25") (pin "14") (pinfunction "6Q_14") (pintype "tri_state"))
      (node (ref "R118") (pin "1") (pinfunction "1_1") (pintype "passive"))
    )
    (net (code "150") (name "Net-(IC25A-7Q)") (class "Default")
      (node (ref "IC25") (pin "13") (pinfunction "7Q_13") (pintype "tri_state"))
      (node (ref "R119") (pin "1") (pinfunction "1_1") (pintype "passive"))
    )
    (net (code "151") (name "Net-(IC26A-1Q)") (class "Default")
      (node (ref "IC26") (pin "19") (pinfunction "1Q_19") (pintype "tri_state"))
      (node (ref "R120") (pin "1") (pinfunction "1_1") (pintype "passive"))
    )
    (net (code "152") (name "Net-(IC26A-2Q)") (class "Default")
      (node (ref "IC26") (pin "18") (pinfunction "2Q_18") (pintype "tri_state"))
      (node (ref "R121") (pin "1") (pinfunction "1_1") (pintype "passive"))
    )
    (net (code "153") (name "Net-(IC26A-3Q)") (class "Default")
      (node (ref "IC26") (pin "17") (pinfunction "3Q_17") (pintype "tri_state"))
      (node (ref "R122") (pin "1") (pinfunction "1_1") (pintype "passive"))
    )
    (net (code "154") (name "Net-(IC26A-4Q)") (class "Default")
      (node (ref "IC26") (pin "16") (pinfunction "4Q_16") (pintype "tri_state"))
      (node (ref "R123") (pin "1") (pinfunction "1_1") (pintype "passive"))
    )
    (net (code "155") (name "Net-(IC26A-5Q)") (class "Default")
      (node (ref "IC26") (pin "15") (pinfunction "5Q_15") (pintype "tri_state"))
      (node (ref "R124") (pin "1") (pinfunction "1_1") (pintype "passive"))
    )
    (net (code "156") (name "Net-(IC26A-6Q)") (class "Default")
      (node (ref "IC26") (pin "14") (pinfunction "6Q_14") (pintype "tri_state"))
      (node (ref "R125") (pin "1") (pinfunction "1_1") (pintype "passive"))
    )
    (net (code "157") (name "Net-(IC26A-7Q)") (class "Default")
      (node (ref "IC26") (pin "13") (pinfunction "7Q_13") (pintype "tri_state"))
      (node (ref "R126") (pin "1") (pinfunction "1_1") (pintype "passive"))
    )
    (net (code "158") (name "Net-(LED1-A)") (class "Default")
      (node (ref "LED1") (pin "7") (pinfunction "A_7") (pintype "passive"))
      (node (ref "R1") (pin "2") (pinfunction "2_2") (pintype "passive"))
    )
    (net (code "159") (name "Net-(LED1-B)") (class "Default")
      (node (ref "LED1") (pin "6") (pinfunction "B_6") (pintype "passive"))
      (node (ref "R2") (pin "2") (pinfunction "2_2") (pintype "passive"))
    )
    (net (code "160") (name "Net-(LED1-C)") (class "Default")
      (node (ref "LED1") (pin "4") (pinfunction "C_4") (pintype "passive"))
      (node (ref "R3") (pin "2") (pinfunction "2_2") (pintype "passive"))
    )
    (net (code "161") (name "Net-(LED1-D)") (class "Default")
      (node (ref "LED1") (pin "2") (pinfunction "D_2") (pintype "passive"))
      (node (ref "R4") (pin "2") (pinfunction "2_2") (pintype "passive"))
    )
    (net (code "162") (name "Net-(LED1-E)") (class "Default")
      (node (ref "LED1") (pin "1") (pinfunction "E_1") (pintype "passive"))
      (node (ref "R5") (pin "2") (pinfunction "2_2") (pintype "passive"))
    )
    (net (code "163") (name "Net-(LED1-F)") (class "Default")
      (node (ref "LED1") (pin "9") (pinfunction "F_9") (pintype "passive"))
      (node (ref "R6") (pin "2") (pinfunction "2_2") (pintype "passive"))
    )
    (net (code "164") (name "Net-(LED1-G)") (class "Default")
      (node (ref "LED1") (pin "10") (pinfunction "G_10") (pintype "passive"))
      (node (ref "R7") (pin "2") (pinfunction "2_2") (pintype "passive"))
    )
    (net (code "165") (name "Net-(LED2-A)") (class "Default")
      (node (ref "LED2") (pin "7") (pinfunction "A_7") (pintype "passive"))
      (node (ref "R8") (pin "2") (pinfunction "2_2") (pintype "passive"))
    )
    (net (code "166") (name "Net-(LED2-B)") (class "Default")
      (node (ref "LED2") (pin "6") (pinfunction "B_6") (pintype "passive"))
      (node (ref "R9") (pin "2") (pinfunction "2_2") (pintype "passive"))
    )
    (net (code "167") (name "Net-(LED2-C)") (class "Default")
      (node (ref "LED2") (pin "4") (pinfunction "C_4") (pintype "passive"))
      (node (ref "R10") (pin "2") (pinfunction "2_2") (pintype "passive"))
    )
    (net (code "168") (name "Net-(LED2-D)") (class "Default")
      (node (ref "LED2") (pin "2") (pinfunction "D_2") (pintype "passive"))
      (node (ref "R11") (pin "2") (pinfunction "2_2") (pintype "passive"))
    )
    (net (code "169") (name "Net-(LED2-E)") (class "Default")
      (node (ref "LED2") (pin "1") (pinfunction "E_1") (pintype "passive"))
      (node (ref "R12") (pin "2") (pinfunction "2_2") (pintype "passive"))
    )
    (net (code "170") (name "Net-(LED2-F)") (class "Default")
      (node (ref "LED2") (pin "9") (pinfunction "F_9") (pintype "passive"))
      (node (ref "R13") (pin "2") (pinfunction "2_2") (pintype "passive"))
    )
    (net (code "171") (name "Net-(LED2-G)") (class "Default")
      (node (ref "LED2") (pin "10") (pinfunction "G_10") (pintype "passive"))
      (node (ref "R14") (pin "2") (pinfunction "2_2") (pintype "passive"))
    )
    (net (code "172") (name "Net-(LED3-A)") (class "Default")
      (node (ref "LED3") (pin "7") (pinfunction "A_7") (pintype "passive"))
      (node (ref "R15") (pin "2") (pinfunction "2_2") (pintype "passive"))
    )
    (net (code "173") (name "Net-(LED3-B)") (class "Default")
      (node (ref "LED3") (pin "6") (pinfunction "B_6") (pintype "passive"))
      (node (ref "R16") (pin "2") (pinfunction "2_2") (pintype "passive"))
    )
    (net (code "174") (name "Net-(LED3-C)") (class "Default")
      (node (ref "LED3") (pin "4") (pinfunction "C_4") (pintype "passive"))
      (node (ref "R17") (pin "2") (pinfunction "2_2") (pintype "passive"))
    )
    (net (code "175") (name "Net-(LED3-D)") (class "Default")
      (node (ref "LED3") (pin "2") (pinfunction "D_2") (pintype "passive"))
      (node (ref "R18") (pin "2") (pinfunction "2_2") (pintype "passive"))
    )
    (net (code "176") (name "Net-(LED3-E)") (class "Default")
      (node (ref "LED3") (pin "1") (pinfunction "E_1") (pintype "passive"))
      (node (ref "R19") (pin "2") (pinfunction "2_2") (pintype "passive"))
    )
    (net (code "177") (name "Net-(LED3-F)") (class "Default")
      (node (ref "LED3") (pin "9") (pinfunction "F_9") (pintype "passive"))
      (node (ref "R20") (pin "2") (pinfunction "2_2") (pintype "passive"))
    )
    (net (code "178") (name "Net-(LED3-G)") (class "Default")
      (node (ref "LED3") (pin "10") (pinfunction "G_10") (pintype "passive"))
      (node (ref "R21") (pin "2") (pinfunction "2_2") (pintype "passive"))
    )
    (net (code "179") (name "Net-(LED4-A)") (class "Default")
      (node (ref "LED4") (pin "7") (pinfunction "A_7") (pintype "passive"))
      (node (ref "R22") (pin "2") (pinfunction "2_2") (pintype "passive"))
    )
    (net (code "180") (name "Net-(LED4-B)") (class "Default")
      (node (ref "LED4") (pin "6") (pinfunction "B_6") (pintype "passive"))
      (node (ref "R23") (pin "2") (pinfunction "2_2") (pintype "passive"))
    )
    (net (code "181") (name "Net-(LED4-C)") (class "Default")
      (node (ref "LED4") (pin "4") (pinfunction "C_4") (pintype "passive"))
      (node (ref "R24") (pin "2") (pinfunction "2_2") (pintype "passive"))
    )
    (net (code "182") (name "Net-(LED4-D)") (class "Default")
      (node (ref "LED4") (pin "2") (pinfunction "D_2") (pintype "passive"))
      (node (ref "R25") (pin "2") (pinfunction "2_2") (pintype "passive"))
    )
    (net (code "183") (name "Net-(LED4-E)") (class "Default")
      (node (ref "LED4") (pin "1") (pinfunction "E_1") (pintype "passive"))
      (node (ref "R26") (pin "2") (pinfunction "2_2") (pintype "passive"))
    )
    (net (code "184") (name "Net-(LED4-F)") (class "Default")
      (node (ref "LED4") (pin "9") (pinfunction "F_9") (pintype "passive"))
      (node (ref "R27") (pin "2") (pinfunction "2_2") (pintype "passive"))
    )
    (net (code "185") (name "Net-(LED4-G)") (class "Default")
      (node (ref "LED4") (pin "10") (pinfunction "G_10") (pintype "passive"))
      (node (ref "R28") (pin "2") (pinfunction "2_2") (pintype "passive"))
    )
    (net (code "186") (name "Net-(LED5-A)") (class "Default")
      (node (ref "LED5") (pin "7") (pinfunction "A_7") (pintype "passive"))
      (node (ref "R29") (pin "2") (pinfunction "2_2") (pintype "passive"))
    )
    (net (code "187") (name "Net-(LED5-B)") (class "Default")
      (node (ref "LED5") (pin "6") (pinfunction "B_6") (pintype "passive"))
      (node (ref "R30") (pin "2") (pinfunction "2_2") (pintype "passive"))
    )
    (net (code "188") (name "Net-(LED5-C)") (class "Default")
      (node (ref "LED5") (pin "4") (pinfunction "C_4") (pintype "passive"))
      (node (ref "R31") (pin "2") (pinfunction "2_2") (pintype "passive"))
    )
    (net (code "189") (name "Net-(LED5-D)") (class "Default")
      (node (ref "LED5") (pin "2") (pinfunction "D_2") (pintype "passive"))
      (node (ref "R32") (pin "2") (pinfunction "2_2") (pintype "passive"))
    )
    (net (code "190") (name "Net-(LED5-E)") (class "Default")
      (node (ref "LED5") (pin "1") (pinfunction "E_1") (pintype "passive"))
      (node (ref "R33") (pin "2") (pinfunction "2_2") (pintype "passive"))
    )
    (net (code "191") (name "Net-(LED5-F)") (class "Default")
      (node (ref "LED5") (pin "9") (pinfunction "F_9") (pintype "passive"))
      (node (ref "R34") (pin "2") (pinfunction "2_2") (pintype "passive"))
    )
    (net (code "192") (name "Net-(LED5-G)") (class "Default")
      (node (ref "LED5") (pin "10") (pinfunction "G_10") (pintype "passive"))
      (node (ref "R35") (pin "2") (pinfunction "2_2") (pintype "passive"))
    )
    (net (code "193") (name "Net-(LED6-A)") (class "Default")
      (node (ref "LED6") (pin "7") (pinfunction "A_7") (pintype "passive"))
      (node (ref "R36") (pin "2") (pinfunction "2_2") (pintype "passive"))
    )
    (net (code "194") (name "Net-(LED6-B)") (class "Default")
      (node (ref "LED6") (pin "6") (pinfunction "B_6") (pintype "passive"))
      (node (ref "R37") (pin "2") (pinfunction "2_2") (pintype "passive"))
    )
    (net (code "195") (name "Net-(LED6-C)") (class "Default")
      (node (ref "LED6") (pin "4") (pinfunction "C_4") (pintype "passive"))
      (node (ref "R38") (pin "2") (pinfunction "2_2") (pintype "passive"))
    )
    (net (code "196") (name "Net-(LED6-D)") (class "Default")
      (node (ref "LED6") (pin "2") (pinfunction "D_2") (pintype "passive"))
      (node (ref "R39") (pin "2") (pinfunction "2_2") (pintype "passive"))
    )
    (net (code "197") (name "Net-(LED6-E)") (class "Default")
      (node (ref "LED6") (pin "1") (pinfunction "E_1") (pintype "passive"))
      (node (ref "R40") (pin "2") (pinfunction "2_2") (pintype "passive"))
    )
    (net (code "198") (name "Net-(LED6-F)") (class "Default")
      (node (ref "LED6") (pin "9") (pinfunction "F_9") (pintype "passive"))
      (node (ref "R41") (pin "2") (pinfunction "2_2") (pintype "passive"))
    )
    (net (code "199") (name "Net-(LED6-G)") (class "Default")
      (node (ref "LED6") (pin "10") (pinfunction "G_10") (pintype "passive"))
      (node (ref "R42") (pin "2") (pinfunction "2_2") (pintype "passive"))
    )
    (net (code "200") (name "Net-(LED7-A)") (class "Default")
      (node (ref "LED7") (pin "7") (pinfunction "A_7") (pintype "passive"))
      (node (ref "R43") (pin "2") (pinfunction "2_2") (pintype "passive"))
    )
    (net (code "201") (name "Net-(LED7-B)") (class "Default")
      (node (ref "LED7") (pin "6") (pinfunction "B_6") (pintype "passive"))
      (node (ref "R44") (pin "2") (pinfunction "2_2") (pintype "passive"))
    )
    (net (code "202") (name "Net-(LED7-C)") (class "Default")
      (node (ref "LED7") (pin "4") (pinfunction "C_4") (pintype "passive"))
      (node (ref "R45") (pin "2") (pinfunction "2_2") (pintype "passive"))
    )
    (net (code "203") (name "Net-(LED7-D)") (class "Default")
      (node (ref "LED7") (pin "2") (pinfunction "D_2") (pintype "passive"))
      (node (ref "R46") (pin "2") (pinfunction "2_2") (pintype "passive"))
    )
    (net (code "204") (name "Net-(LED7-E)") (class "Default")
      (node (ref "LED7") (pin "1") (pinfunction "E_1") (pintype "passive"))
      (node (ref "R47") (pin "2") (pinfunction "2_2") (pintype "passive"))
    )
    (net (code "205") (name "Net-(LED7-F)") (class "Default")
      (node (ref "LED7") (pin "9") (pinfunction "F_9") (pintype "passive"))
      (node (ref "R48") (pin "2") (pinfunction "2_2") (pintype "passive"))
    )
    (net (code "206") (name "Net-(LED7-G)") (class "Default")
      (node (ref "LED7") (pin "10") (pinfunction "G_10") (pintype "passive"))
      (node (ref "R49") (pin "2") (pinfunction "2_2") (pintype "passive"))
    )
    (net (code "207") (name "Net-(LED8-A)") (class "Default")
      (node (ref "LED8") (pin "7") (pinfunction "A_7") (pintype "passive"))
      (node (ref "R50") (pin "2") (pinfunction "2_2") (pintype "passive"))
    )
    (net (code "208") (name "Net-(LED8-B)") (class "Default")
      (node (ref "LED8") (pin "6") (pinfunction "B_6") (pintype "passive"))
      (node (ref "R51") (pin "2") (pinfunction "2_2") (pintype "passive"))
    )
    (net (code "209") (name "Net-(LED8-C)") (class "Default")
      (node (ref "LED8") (pin "4") (pinfunction "C_4") (pintype "passive"))
      (node (ref "R52") (pin "2") (pinfunction "2_2") (pintype "passive"))
    )
    (net (code "210") (name "Net-(LED8-D)") (class "Default")
      (node (ref "LED8") (pin "2") (pinfunction "D_2") (pintype "passive"))
      (node (ref "R53") (pin "2") (pinfunction "2_2") (pintype "passive"))
    )
    (net (code "211") (name "Net-(LED8-E)") (class "Default")
      (node (ref "LED8") (pin "1") (pinfunction "E_1") (pintype "passive"))
      (node (ref "R54") (pin "2") (pinfunction "2_2") (pintype "passive"))
    )
    (net (code "212") (name "Net-(LED8-F)") (class "Default")
      (node (ref "LED8") (pin "9") (pinfunction "F_9") (pintype "passive"))
      (node (ref "R55") (pin "2") (pinfunction "2_2") (pintype "passive"))
    )
    (net (code "213") (name "Net-(LED8-G)") (class "Default")
      (node (ref "LED8") (pin "10") (pinfunction "G_10") (pintype "passive"))
      (node (ref "R56") (pin "2") (pinfunction "2_2") (pintype "passive"))
    )
    (net (code "214") (name "Net-(LED11-A)") (class "Default")
      (node (ref "LED11") (pin "7") (pinfunction "A_7") (pintype "passive"))
      (node (ref "R71") (pin "2") (pinfunction "2_2") (pintype "passive"))
    )
    (net (code "215") (name "Net-(LED11-B)") (class "Default")
      (node (ref "LED11") (pin "6") (pinfunction "B_6") (pintype "passive"))
      (node (ref "R72") (pin "2") (pinfunction "2_2") (pintype "passive"))
    )
    (net (code "216") (name "Net-(LED11-C)") (class "Default")
      (node (ref "LED11") (pin "4") (pinfunction "C_4") (pintype "passive"))
      (node (ref "R73") (pin "2") (pinfunction "2_2") (pintype "passive"))
    )
    (net (code "217") (name "Net-(LED11-D)") (class "Default")
      (node (ref "LED11") (pin "2") (pinfunction "D_2") (pintype "passive"))
      (node (ref "R74") (pin "2") (pinfunction "2_2") (pintype "passive"))
    )
    (net (code "218") (name "Net-(LED11-E)") (class "Default")
      (node (ref "LED11") (pin "1") (pinfunction "E_1") (pintype "passive"))
      (node (ref "R75") (pin "2") (pinfunction "2_2") (pintype "passive"))
    )
    (net (code "219") (name "Net-(LED11-F)") (class "Default")
      (node (ref "LED11") (pin "9") (pinfunction "F_9") (pintype "passive"))
      (node (ref "R76") (pin "2") (pinfunction "2_2") (pintype "passive"))
    )
    (net (code "220") (name "Net-(LED11-G)") (class "Default")
      (node (ref "LED11") (pin "10") (pinfunction "G_10") (pintype "passive"))
      (node (ref "R77") (pin "2") (pinfunction "2_2") (pintype "passive"))
    )
    (net (code "221") (name "Net-(LED12-A)") (class "Default")
      (node (ref "LED12") (pin "7") (pinfunction "A_7") (pintype "passive"))
      (node (ref "R78") (pin "2") (pinfunction "2_2") (pintype "passive"))
    )
    (net (code "222") (name "Net-(LED12-B)") (class "Default")
      (node (ref "LED12") (pin "6") (pinfunction "B_6") (pintype "passive"))
      (node (ref "R79") (pin "2") (pinfunction "2_2") (pintype "passive"))
    )
    (net (code "223") (name "Net-(LED12-C)") (class "Default")
      (node (ref "LED12") (pin "4") (pinfunction "C_4") (pintype "passive"))
      (node (ref "R80") (pin "2") (pinfunction "2_2") (pintype "passive"))
    )
    (net (code "224") (name "Net-(LED12-D)") (class "Default")
      (node (ref "LED12") (pin "2") (pinfunction "D_2") (pintype "passive"))
      (node (ref "R81") (pin "2") (pinfunction "2_2") (pintype "passive"))
    )
    (net (code "225") (name "Net-(LED12-E)") (class "Default")
      (node (ref "LED12") (pin "1") (pinfunction "E_1") (pintype "passive"))
      (node (ref "R82") (pin "2") (pinfunction "2_2") (pintype "passive"))
    )
    (net (code "226") (name "Net-(LED12-F)") (class "Default")
      (node (ref "LED12") (pin "9") (pinfunction "F_9") (pintype "passive"))
      (node (ref "R83") (pin "2") (pinfunction "2_2") (pintype "passive"))
    )
    (net (code "227") (name "Net-(LED12-G)") (class "Default")
      (node (ref "LED12") (pin "10") (pinfunction "G_10") (pintype "passive"))
      (node (ref "R84") (pin "2") (pinfunction "2_2") (pintype "passive"))
    )
    (net (code "228") (name "Net-(LED13-A)") (class "Default")
      (node (ref "LED13") (pin "7") (pinfunction "A_7") (pintype "passive"))
      (node (ref "R85") (pin "2") (pinfunction "2_2") (pintype "passive"))
    )
    (net (code "229") (name "Net-(LED13-B)") (class "Default")
      (node (ref "LED13") (pin "6") (pinfunction "B_6") (pintype "passive"))
      (node (ref "R86") (pin "2") (pinfunction "2_2") (pintype "passive"))
    )
    (net (code "230") (name "Net-(LED13-C)") (class "Default")
      (node (ref "LED13") (pin "4") (pinfunction "C_4") (pintype "passive"))
      (node (ref "R87") (pin "2") (pinfunction "2_2") (pintype "passive"))
    )
    (net (code "231") (name "Net-(LED13-D)") (class "Default")
      (node (ref "LED13") (pin "2") (pinfunction "D_2") (pintype "passive"))
      (node (ref "R88") (pin "2") (pinfunction "2_2") (pintype "passive"))
    )
    (net (code "232") (name "Net-(LED13-E)") (class "Default")
      (node (ref "LED13") (pin "1") (pinfunction "E_1") (pintype "passive"))
      (node (ref "R89") (pin "2") (pinfunction "2_2") (pintype "passive"))
    )
    (net (code "233") (name "Net-(LED13-F)") (class "Default")
      (node (ref "LED13") (pin "9") (pinfunction "F_9") (pintype "passive"))
      (node (ref "R90") (pin "2") (pinfunction "2_2") (pintype "passive"))
    )
    (net (code "234") (name "Net-(LED13-G)") (class "Default")
      (node (ref "LED13") (pin "10") (pinfunction "G_10") (pintype "passive"))
      (node (ref "R91") (pin "2") (pinfunction "2_2") (pintype "passive"))
    )
    (net (code "235") (name "Net-(LED14-A)") (class "Default")
      (node (ref "LED14") (pin "7") (pinfunction "A_7") (pintype "passive"))
      (node (ref "R92") (pin "2") (pinfunction "2_2") (pintype "passive"))
    )
    (net (code "236") (name "Net-(LED14-B)") (class "Default")
      (node (ref "LED14") (pin "6") (pinfunction "B_6") (pintype "passive"))
      (node (ref "R93") (pin "2") (pinfunction "2_2") (pintype "passive"))
    )
    (net (code "237") (name "Net-(LED14-C)") (class "Default")
      (node (ref "LED14") (pin "4") (pinfunction "C_4") (pintype "passive"))
      (node (ref "R94") (pin "2") (pinfunction "2_2") (pintype "passive"))
    )
    (net (code "238") (name "Net-(LED14-D)") (class "Default")
      (node (ref "LED14") (pin "2") (pinfunction "D_2") (pintype "passive"))
      (node (ref "R95") (pin "2") (pinfunction "2_2") (pintype "passive"))
    )
    (net (code "239") (name "Net-(LED14-E)") (class "Default")
      (node (ref "LED14") (pin "1") (pinfunction "E_1") (pintype "passive"))
      (node (ref "R96") (pin "2") (pinfunction "2_2") (pintype "passive"))
    )
    (net (code "240") (name "Net-(LED14-F)") (class "Default")
      (node (ref "LED14") (pin "9") (pinfunction "F_9") (pintype "passive"))
      (node (ref "R97") (pin "2") (pinfunction "2_2") (pintype "passive"))
    )
    (net (code "241") (name "Net-(LED14-G)") (class "Default")
      (node (ref "LED14") (pin "10") (pinfunction "G_10") (pintype "passive"))
      (node (ref "R98") (pin "2") (pinfunction "2_2") (pintype "passive"))
    )
    (net (code "242") (name "Net-(LED15-A)") (class "Default")
      (node (ref "LED15") (pin "7") (pinfunction "A_7") (pintype "passive"))
      (node (ref "R99") (pin "2") (pinfunction "2_2") (pintype "passive"))
    )
    (net (code "243") (name "Net-(LED15-B)") (class "Default")
      (node (ref "LED15") (pin "6") (pinfunction "B_6") (pintype "passive"))
      (node (ref "R100") (pin "2") (pinfunction "2_2") (pintype "passive"))
    )
    (net (code "244") (name "Net-(LED15-C)") (class "Default")
      (node (ref "LED15") (pin "4") (pinfunction "C_4") (pintype "passive"))
      (node (ref "R101") (pin "2") (pinfunction "2_2") (pintype "passive"))
    )
    (net (code "245") (name "Net-(LED15-D)") (class "Default")
      (node (ref "LED15") (pin "2") (pinfunction "D_2") (pintype "passive"))
      (node (ref "R102") (pin "2") (pinfunction "2_2") (pintype "passive"))
    )
    (net (code "246") (name "Net-(LED15-E)") (class "Default")
      (node (ref "LED15") (pin "1") (pinfunction "E_1") (pintype "passive"))
      (node (ref "R103") (pin "2") (pinfunction "2_2") (pintype "passive"))
    )
    (net (code "247") (name "Net-(LED15-F)") (class "Default")
      (node (ref "LED15") (pin "9") (pinfunction "F_9") (pintype "passive"))
      (node (ref "R104") (pin "2") (pinfunction "2_2") (pintype "passive"))
    )
    (net (code "248") (name "Net-(LED15-G)") (class "Default")
      (node (ref "LED15") (pin "10") (pinfunction "G_10") (pintype "passive"))
      (node (ref "R105") (pin "2") (pinfunction "2_2") (pintype "passive"))
    )
    (net (code "249") (name "Net-(LED16-A)") (class "Default")
      (node (ref "LED16") (pin "7") (pinfunction "A_7") (pintype "passive"))
      (node (ref "R106") (pin "2") (pinfunction "2_2") (pintype "passive"))
    )
    (net (code "250") (name "Net-(LED16-B)") (class "Default")
      (node (ref "LED16") (pin "6") (pinfunction "B_6") (pintype "passive"))
      (node (ref "R107") (pin "2") (pinfunction "2_2") (pintype "passive"))
    )
    (net (code "251") (name "Net-(LED16-C)") (class "Default")
      (node (ref "LED16") (pin "4") (pinfunction "C_4") (pintype "passive"))
      (node (ref "R108") (pin "2") (pinfunction "2_2") (pintype "passive"))
    )
    (net (code "252") (name "Net-(LED16-D)") (class "Default")
      (node (ref "LED16") (pin "2") (pinfunction "D_2") (pintype "passive"))
      (node (ref "R109") (pin "2") (pinfunction "2_2") (pintype "passive"))
    )
    (net (code "253") (name "Net-(LED16-E)") (class "Default")
      (node (ref "LED16") (pin "1") (pinfunction "E_1") (pintype "passive"))
      (node (ref "R110") (pin "2") (pinfunction "2_2") (pintype "passive"))
    )
    (net (code "254") (name "Net-(LED16-F)") (class "Default")
      (node (ref "LED16") (pin "9") (pinfunction "F_9") (pintype "passive"))
      (node (ref "R111") (pin "2") (pinfunction "2_2") (pintype "passive"))
    )
    (net (code "255") (name "Net-(LED16-G)") (class "Default")
      (node (ref "LED16") (pin "10") (pinfunction "G_10") (pintype "passive"))
      (node (ref "R112") (pin "2") (pinfunction "2_2") (pintype "passive"))
    )
    (net (code "256") (name "Net-(LED17-A)") (class "Default")
      (node (ref "LED17") (pin "7") (pinfunction "A_7") (pintype "passive"))
      (node (ref "R113") (pin "2") (pinfunction "2_2") (pintype "passive"))
    )
    (net (code "257") (name "Net-(LED17-B)") (class "Default")
      (node (ref "LED17") (pin "6") (pinfunction "B_6") (pintype "passive"))
      (node (ref "R114") (pin "2") (pinfunction "2_2") (pintype "passive"))
    )
    (net (code "258") (name "Net-(LED17-C)") (class "Default")
      (node (ref "LED17") (pin "4") (pinfunction "C_4") (pintype "passive"))
      (node (ref "R115") (pin "2") (pinfunction "2_2") (pintype "passive"))
    )
    (net (code "259") (name "Net-(LED17-D)") (class "Default")
      (node (ref "LED17") (pin "2") (pinfunction "D_2") (pintype "passive"))
      (node (ref "R116") (pin "2") (pinfunction "2_2") (pintype "passive"))
    )
    (net (code "260") (name "Net-(LED17-E)") (class "Default")
      (node (ref "LED17") (pin "1") (pinfunction "E_1") (pintype "passive"))
      (node (ref "R117") (pin "2") (pinfunction "2_2") (pintype "passive"))
    )
    (net (code "261") (name "Net-(LED17-F)") (class "Default")
      (node (ref "LED17") (pin "9") (pinfunction "F_9") (pintype "passive"))
      (node (ref "R118") (pin "2") (pinfunction "2_2") (pintype "passive"))
    )
    (net (code "262") (name "Net-(LED17-G)") (class "Default")
      (node (ref "LED17") (pin "10") (pinfunction "G_10") (pintype "passive"))
      (node (ref "R119") (pin "2") (pinfunction "2_2") (pintype "passive"))
    )
    (net (code "263") (name "Net-(LED18-A)") (class "Default")
      (node (ref "LED18") (pin "7") (pinfunction "A_7") (pintype "passive"))
      (node (ref "R120") (pin "2") (pinfunction "2_2") (pintype "passive"))
    )
    (net (code "264") (name "Net-(LED18-B)") (class "Default")
      (node (ref "LED18") (pin "6") (pinfunction "B_6") (pintype "passive"))
      (node (ref "R121") (pin "2") (pinfunction "2_2") (pintype "passive"))
    )
    (net (code "265") (name "Net-(LED18-C)") (class "Default")
      (node (ref "LED18") (pin "4") (pinfunction "C_4") (pintype "passive"))
      (node (ref "R122") (pin "2") (pinfunction "2_2") (pintype "passive"))
    )
    (net (code "266") (name "Net-(LED18-D)") (class "Default")
      (node (ref "LED18") (pin "2") (pinfunction "D_2") (pintype "passive"))
      (node (ref "R123") (pin "2") (pinfunction "2_2") (pintype "passive"))
    )
    (net (code "267") (name "Net-(LED18-E)") (class "Default")
      (node (ref "LED18") (pin "1") (pinfunction "E_1") (pintype "passive"))
      (node (ref "R124") (pin "2") (pinfunction "2_2") (pintype "passive"))
    )
    (net (code "268") (name "Net-(LED18-F)") (class "Default")
      (node (ref "LED18") (pin "9") (pinfunction "F_9") (pintype "passive"))
      (node (ref "R125") (pin "2") (pinfunction "2_2") (pintype "passive"))
    )
    (net (code "269") (name "Net-(LED18-G)") (class "Default")
      (node (ref "LED18") (pin "10") (pinfunction "G_10") (pintype "passive"))
      (node (ref "R126") (pin "2") (pinfunction "2_2") (pintype "passive"))
    )
    (net (code "270") (name "Net-(LED28-PadA)") (class "Default")
      (node (ref "LED28") (pin "A") (pinfunction "A_A") (pintype "passive"))
      (node (ref "R184") (pin "2") (pinfunction "2_2") (pintype "passive"))
    )
    (net (code "271") (name "Net-(LED29-PadA)") (class "Default")
      (node (ref "LED29") (pin "A") (pinfunction "A_A") (pintype "passive"))
      (node (ref "R185") (pin "2") (pinfunction "2_2") (pintype "passive"))
    )
    (net (code "272") (name "Net-(LED30-PadA)") (class "Default")
      (node (ref "LED30") (pin "A") (pinfunction "A_A") (pintype "passive"))
      (node (ref "R186") (pin "2") (pinfunction "2_2") (pintype "passive"))
    )
    (net (code "273") (name "VCC") (class "Default")
      (node (ref "C1") (pin "1") (pinfunction "1_1") (pintype "passive"))
      (node (ref "C10") (pin "1") (pinfunction "1_1") (pintype "passive"))
      (node (ref "C11") (pin "1") (pinfunction "1_1") (pintype "passive"))
      (node (ref "C12") (pin "1") (pinfunction "1_1") (pintype "passive"))
      (node (ref "C13") (pin "1") (pinfunction "1_1") (pintype "passive"))
      (node (ref "C14") (pin "1") (pinfunction "1_1") (pintype "passive"))
      (node (ref "C15") (pin "1") (pinfunction "1_1") (pintype "passive"))
      (node (ref "C16") (pin "1") (pinfunction "1_1") (pintype "passive"))
      (node (ref "C17") (pin "1") (pinfunction "1_1") (pintype "passive"))
      (node (ref "C18") (pin "1") (pinfunction "1_1") (pintype "passive"))
      (node (ref "C19") (pin "1") (pinfunction "1_1") (pintype "passive"))
      (node (ref "C2") (pin "1") (pinfunction "1_1") (pintype "passive"))
      (node (ref "C20") (pin "1") (pinfunction "1_1") (pintype "passive"))
      (node (ref "C21") (pin "1") (pinfunction "1_1") (pintype "passive"))
      (node (ref "C22") (pin "1") (pinfunction "1_1") (pintype "passive"))
      (node (ref "C23") (pin "1") (pinfunction "1_1") (pintype "passive"))
      (node (ref "C3") (pin "1") (pinfunction "1_1") (pintype "passive"))
      (node (ref "C4") (pin "1") (pinfunction "1_1") (pintype "passive"))
      (node (ref "C5") (pin "1") (pinfunction "1_1") (pintype "passive"))
      (node (ref "C6") (pin "1") (pinfunction "1_1") (pintype "passive"))
      (node (ref "C7") (pin "1") (pinfunction "1_1") (pintype "passive"))
      (node (ref "C8") (pin "1") (pinfunction "1_1") (pintype "passive"))
      (node (ref "C9") (pin "1") (pinfunction "1_1") (pintype "passive"))
      (node (ref "CON6") (pin "1") (pinfunction "1_1") (pintype "passive"))
      (node (ref "CON6") (pin "2") (pinfunction "2_2") (pintype "passive"))
    )
    (net (code "274") (name "unconnected-(IC1A-8Q-Pad12)") (class "Default")
      (node (ref "IC1") (pin "12") (pinfunction "8Q_12") (pintype "tri_state"))
    )
    (net (code "275") (name "unconnected-(IC3A-8Q-Pad12)") (class "Default")
      (node (ref "IC3") (pin "12") (pinfunction "8Q_12") (pintype "tri_state"))
    )
    (net (code "276") (name "unconnected-(IC5A-8Q-Pad12)") (class "Default")
      (node (ref "IC5") (pin "12") (pinfunction "8Q_12") (pintype "tri_state"))
    )
    (net (code "277") (name "unconnected-(IC6A-8Q-Pad12)") (class "Default")
      (node (ref "IC6") (pin "12") (pinfunction "8Q_12") (pintype "tri_state"))
    )
    (net (code "278") (name "unconnected-(IC8A-8Q-Pad12)") (class "Default")
      (node (ref "IC8") (pin "12") (pinfunction "8Q_12") (pintype "tri_state"))
    )
    (net (code "279") (name "unconnected-(IC9A-8Q-Pad12)") (class "Default")
      (node (ref "IC9") (pin "12") (pinfunction "8Q_12") (pintype "tri_state"))
    )
    (net (code "280") (name "unconnected-(IC10A-8Q-Pad12)") (class "Default")
      (node (ref "IC10") (pin "12") (pinfunction "8Q_12") (pintype "tri_state"))
    )
    (net (code "281") (name "unconnected-(IC11A-8Q-Pad12)") (class "Default")
      (node (ref "IC11") (pin "12") (pinfunction "8Q_12") (pintype "tri_state"))
    )
    (net (code "282") (name "unconnected-(IC17A-8Q-Pad12)") (class "Default")
      (node (ref "IC17") (pin "12") (pinfunction "8Q_12") (pintype "tri_state"))
    )
    (net (code "283") (name "unconnected-(IC18A-8Q-Pad12)") (class "Default")
      (node (ref "IC18") (pin "12") (pinfunction "8Q_12") (pintype "tri_state"))
    )
    (net (code "284") (name "unconnected-(IC21A-8Q-Pad12)") (class "Default")
      (node (ref "IC21") (pin "12") (pinfunction "8Q_12") (pintype "tri_state"))
    )
    (net (code "285") (name "unconnected-(IC22A-8Q-Pad12)") (class "Default")
      (node (ref "IC22") (pin "12") (pinfunction "8Q_12") (pintype "tri_state"))
    )
    (net (code "286") (name "unconnected-(IC23A-8Q-Pad12)") (class "Default")
      (node (ref "IC23") (pin "12") (pinfunction "8Q_12") (pintype "tri_state"))
    )
    (net (code "287") (name "unconnected-(IC24A-8Q-Pad12)") (class "Default")
      (node (ref "IC24") (pin "12") (pinfunction "8Q_12") (pintype "tri_state"))
    )
    (net (code "288") (name "unconnected-(IC25A-8Q-Pad12)") (class "Default")
      (node (ref "IC25") (pin "12") (pinfunction "8Q_12") (pintype "tri_state"))
    )
    (net (code "289") (name "unconnected-(IC26A-8Q-Pad12)") (class "Default")
      (node (ref "IC26") (pin "12") (pinfunction "8Q_12") (pintype "tri_state"))
    )
    (net (code "290") (name "unconnected-(LED1-DP-Pad5)") (class "Default")
      (node (ref "LED1") (pin "5") (pinfunction "DP_5") (pintype "passive"))
    )
    (net (code "291") (name "unconnected-(LED2-DP-Pad5)") (class "Default")
      (node (ref "LED2") (pin "5") (pinfunction "DP_5") (pintype "passive"))
    )
    (net (code "292") (name "unconnected-(LED3-DP-Pad5)") (class "Default")
      (node (ref "LED3") (pin "5") (pinfunction "DP_5") (pintype "passive"))
    )
    (net (code "293") (name "unconnected-(LED4-DP-Pad5)") (class "Default")
      (node (ref "LED4") (pin "5") (pinfunction "DP_5") (pintype "passive"))
    )
    (net (code "294") (name "unconnected-(LED5-DP-Pad5)") (class "Default")
      (node (ref "LED5") (pin "5") (pinfunction "DP_5") (pintype "passive"))
    )
    (net (code "295") (name "unconnected-(LED6-DP-Pad5)") (class "Default")
      (node (ref "LED6") (pin "5") (pinfunction "DP_5") (pintype "passive"))
    )
    (net (code "296") (name "unconnected-(LED7-DP-Pad5)") (class "Default")
      (node (ref "LED7") (pin "5") (pinfunction "DP_5") (pintype "passive"))
    )
    (net (code "297") (name "unconnected-(LED8-DP-Pad5)") (class "Default")
      (node (ref "LED8") (pin "5") (pinfunction "DP_5") (pintype "passive"))
    )
    (net (code "298") (name "unconnected-(LED11-DP-Pad5)") (class "Default")
      (node (ref "LED11") (pin "5") (pinfunction "DP_5") (pintype "passive"))
    )
    (net (code "299") (name "unconnected-(LED12-DP-Pad5)") (class "Default")
      (node (ref "LED12") (pin "5") (pinfunction "DP_5") (pintype "passive"))
    )
    (net (code "300") (name "unconnected-(LED13-DP-Pad5)") (class "Default")
      (node (ref "LED13") (pin "5") (pinfunction "DP_5") (pintype "passive"))
    )
    (net (code "301") (name "unconnected-(LED14-DP-Pad5)") (class "Default")
      (node (ref "LED14") (pin "5") (pinfunction "DP_5") (pintype "passive"))
    )
    (net (code "302") (name "unconnected-(LED15-DP-Pad5)") (class "Default")
      (node (ref "LED15") (pin "5") (pinfunction "DP_5") (pintype "passive"))
    )
    (net (code "303") (name "unconnected-(LED16-DP-Pad5)") (class "Default")
      (node (ref "LED16") (pin "5") (pinfunction "DP_5") (pintype "passive"))
    )
    (net (code "304") (name "unconnected-(LED17-DP-Pad5)") (class "Default")
      (node (ref "LED17") (pin "5") (pinfunction "DP_5") (pintype "passive"))
    )
    (net (code "305") (name "unconnected-(LED18-DP-Pad5)") (class "Default")
      (node (ref "LED18") (pin "5") (pinfunction "DP_5") (pintype "passive"))
    )
  )
)
